# Blueberry_Pi.net
KiCad netlist of a schematic drawn in EAGLE
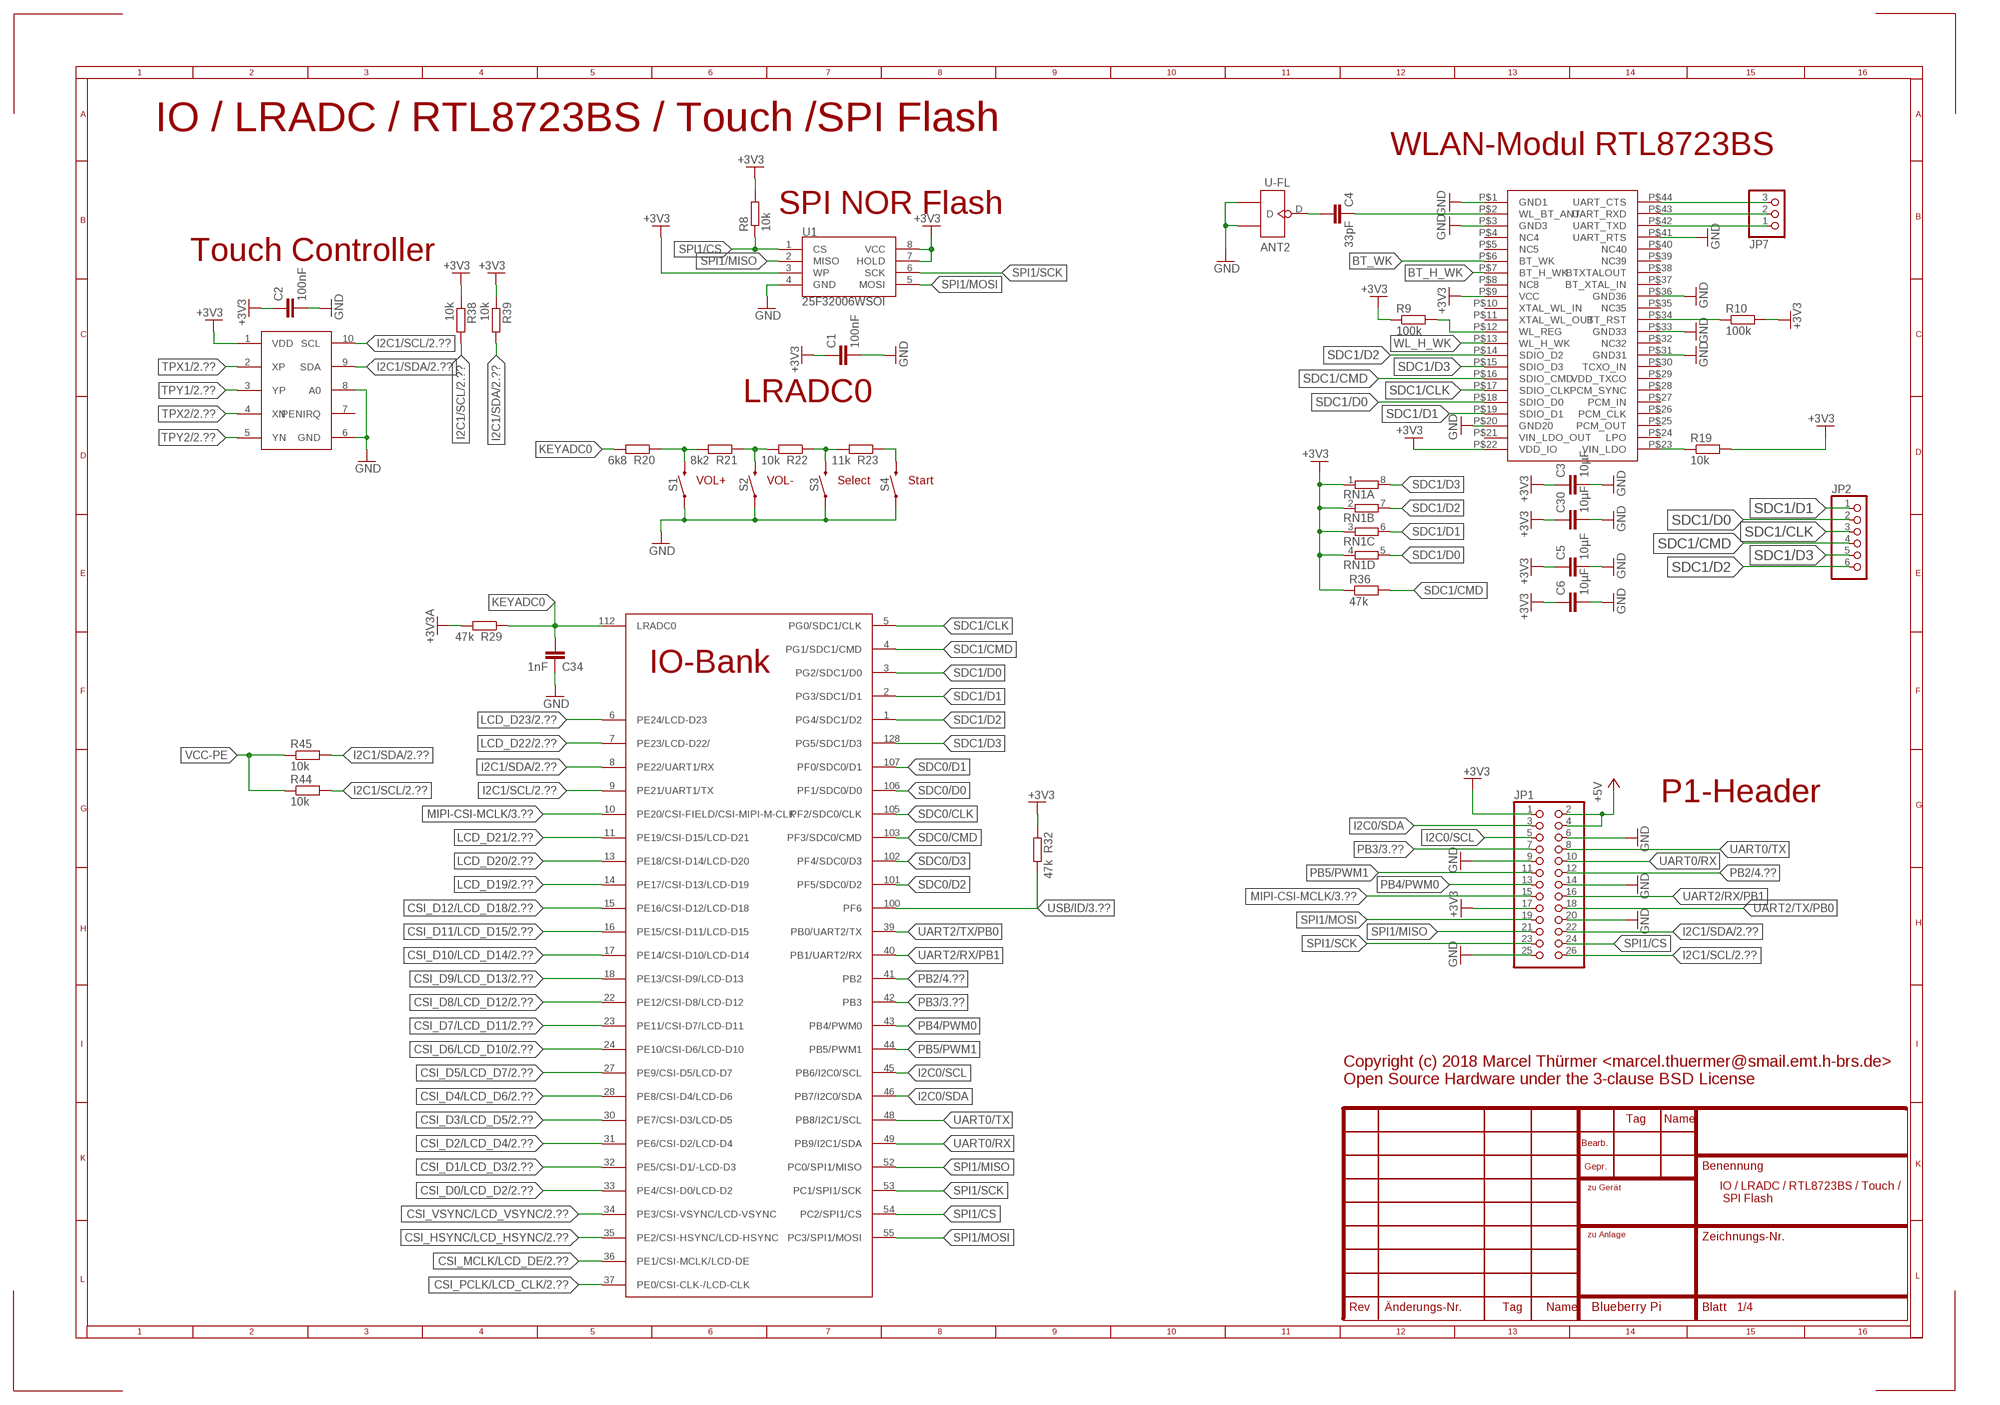
[diagram p0: schematic, sheet 1]
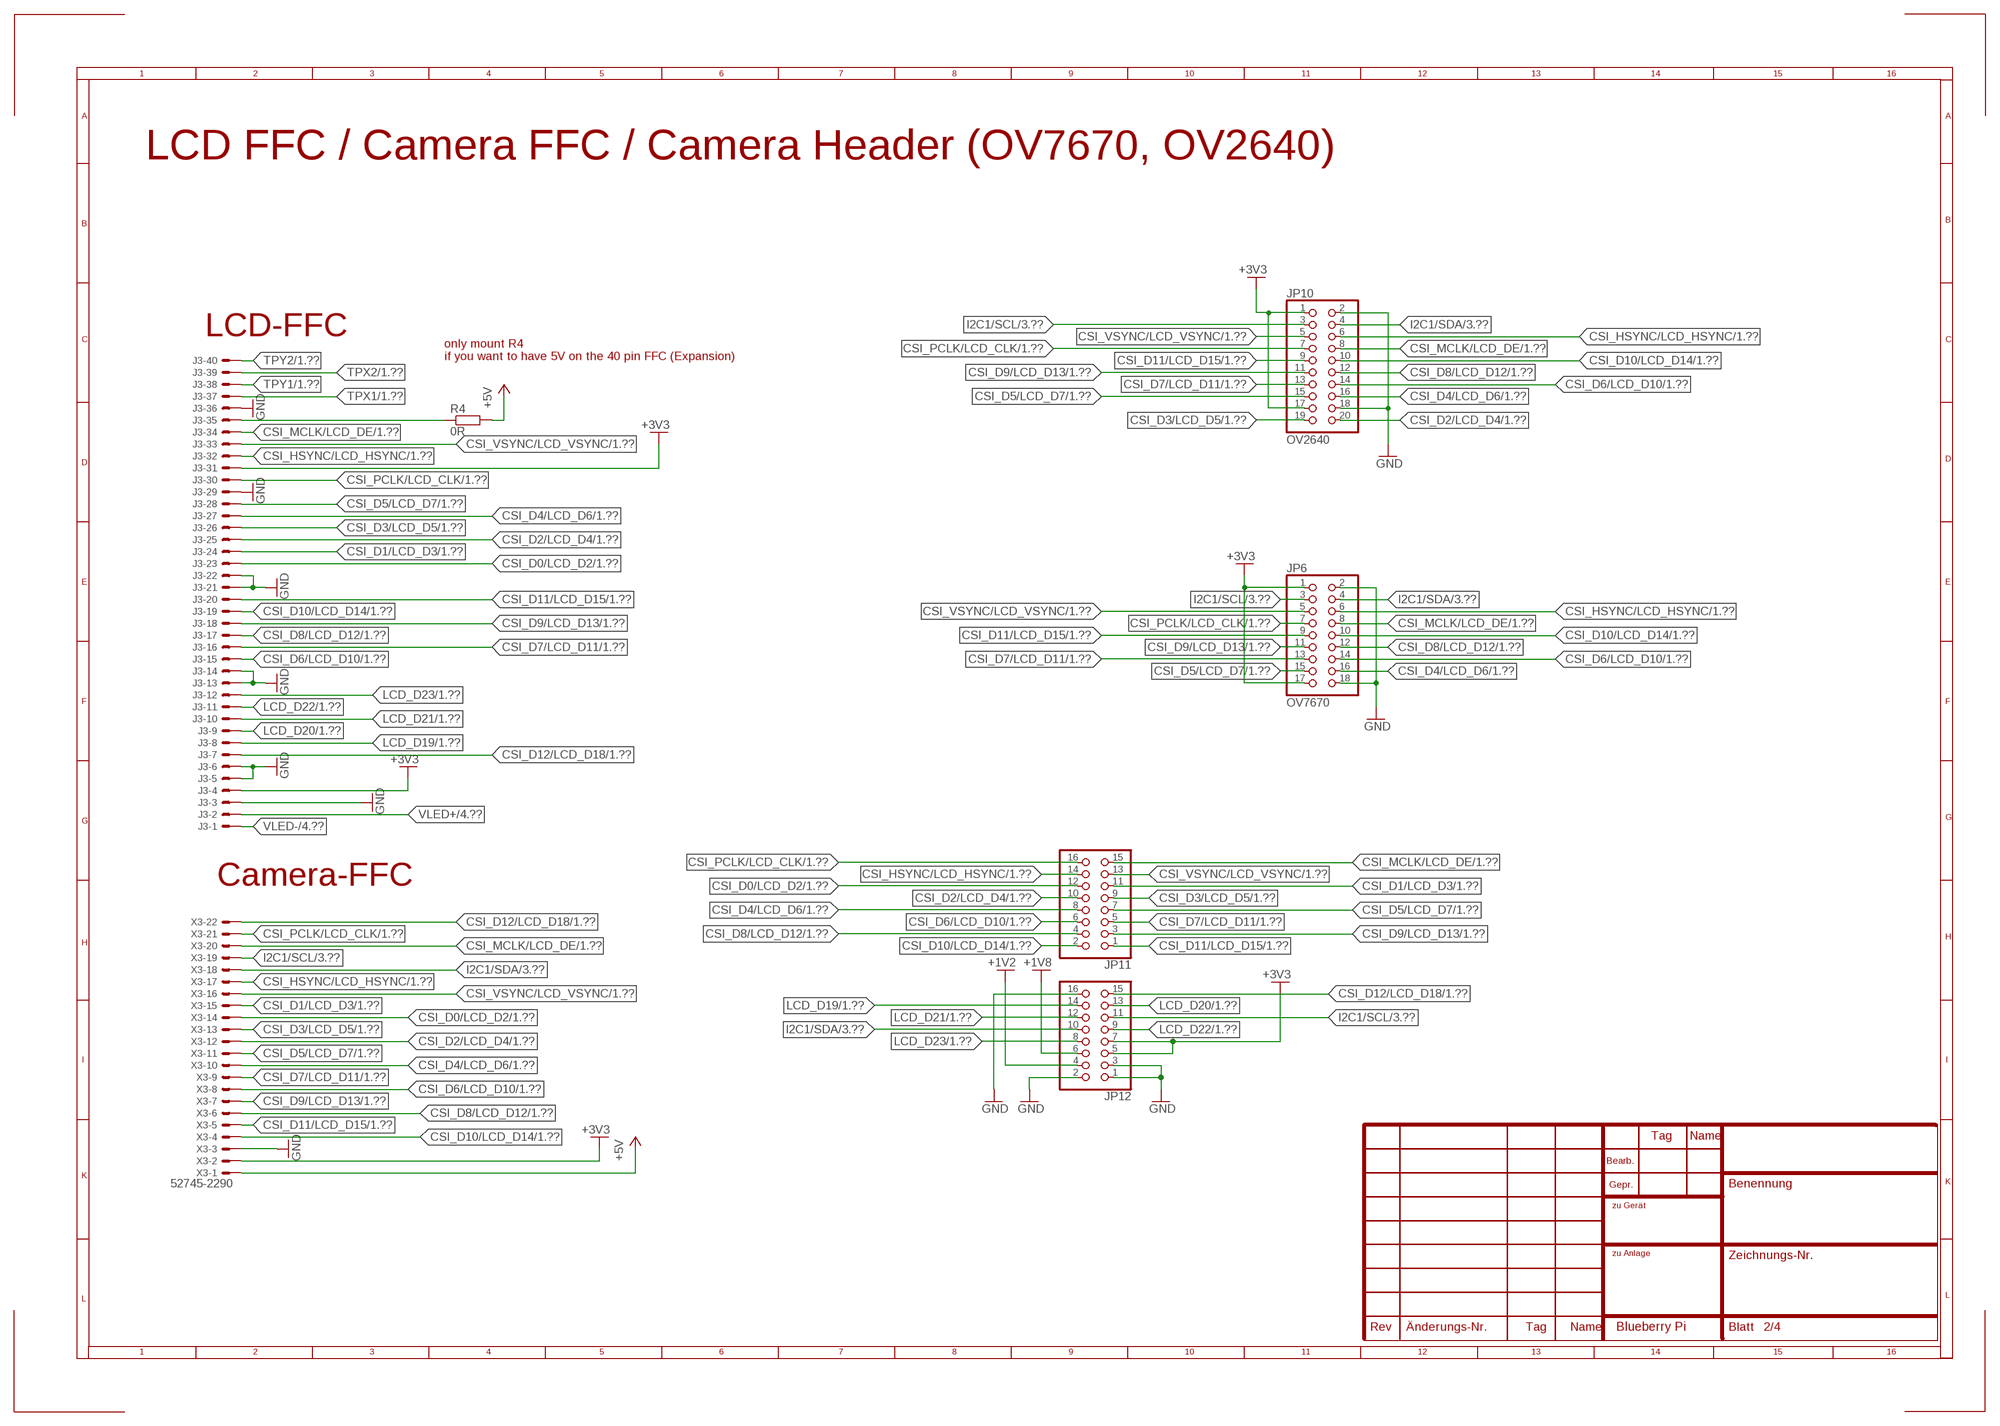
[diagram p1: schematic, sheet 2]
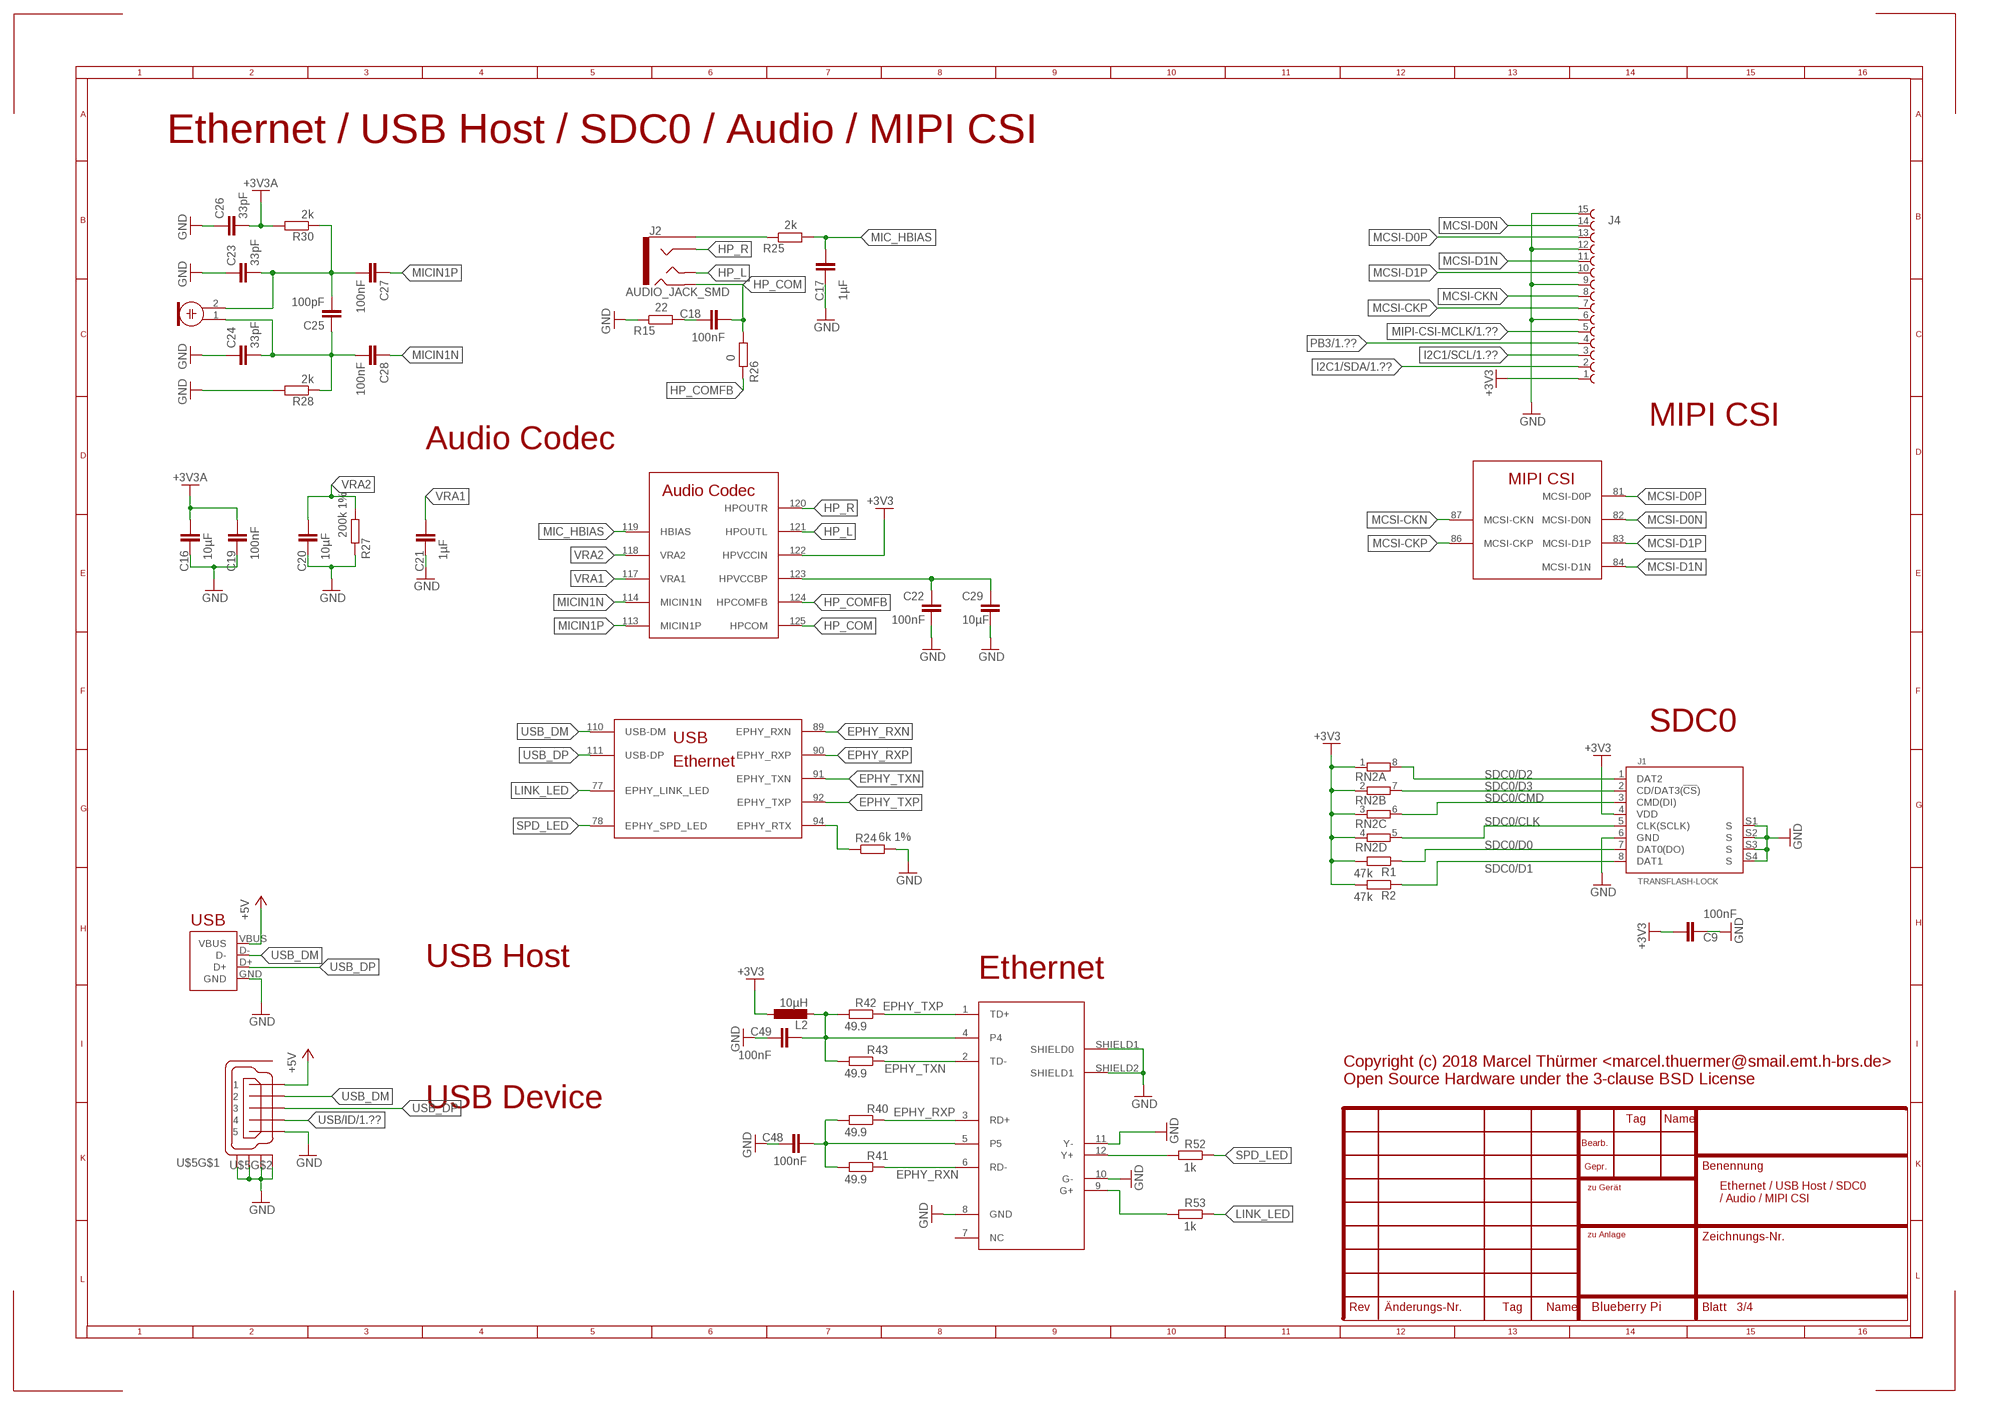
[diagram p2: schematic, sheet 3]
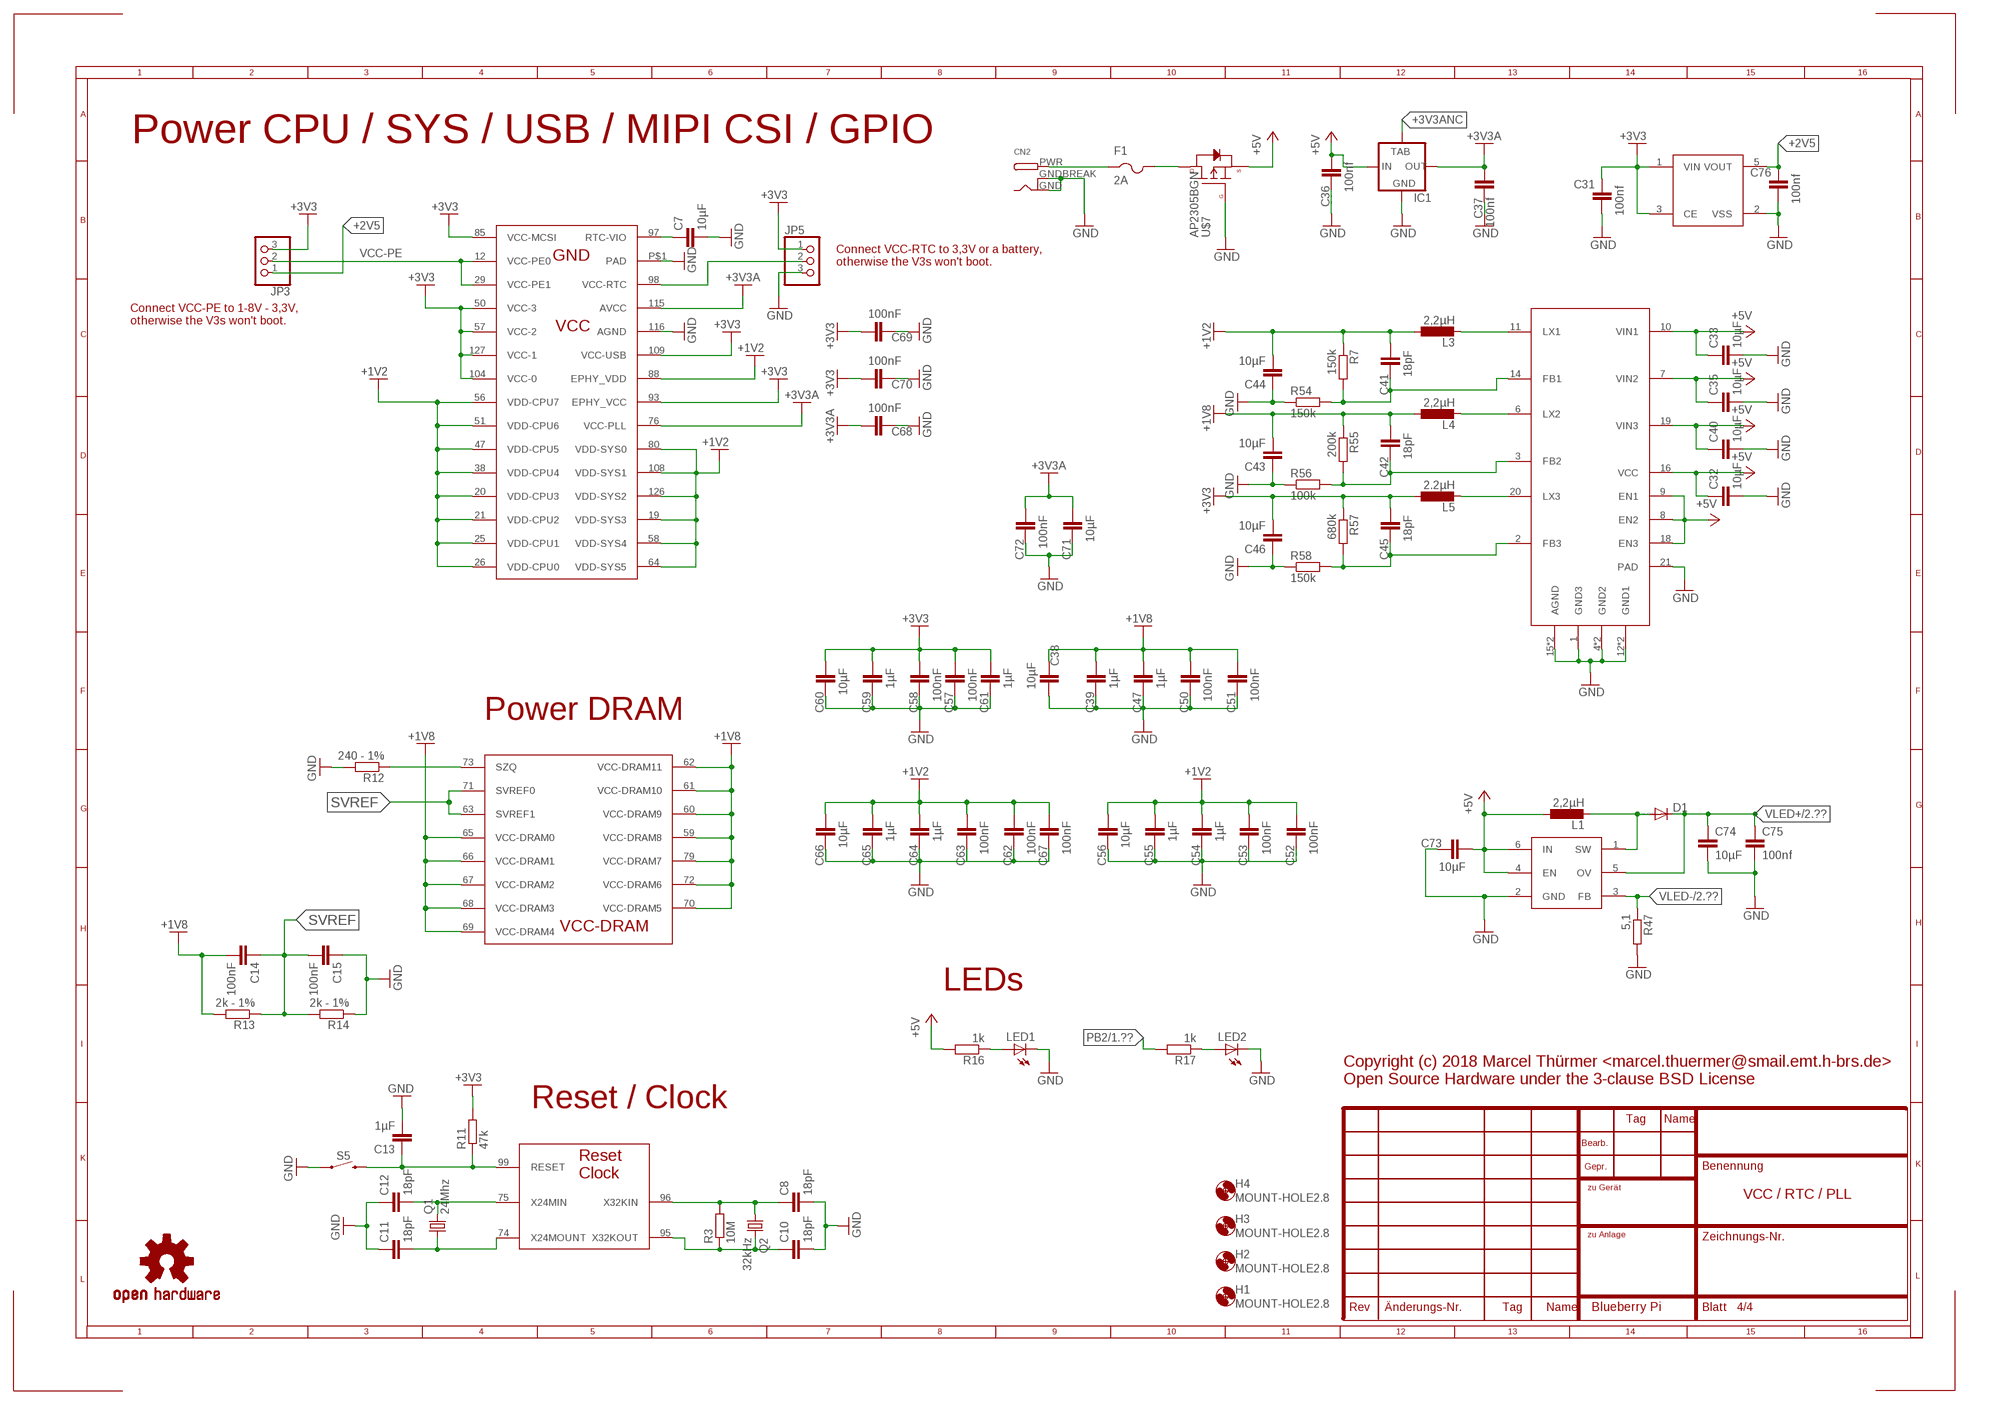
[diagram p3: schematic, sheet 4]

(export (version "E")
  (design (tool "Eeschema 10.0.6"))
  (components
    (comp (ref "C9")
      (value "100nF")
      (footprint "eagle-import:C0603")
      (libsource (lib "eagle-import") (part "C-EUC0603"))
    )
    (comp (ref "C16")
      (value "10µF")
      (footprint "eagle-import:C0805")
      (libsource (lib "eagle-import") (part "C-EUC0805"))
    )
    (comp (ref "C17")
      (value "1µF")
      (footprint "eagle-import:C0603")
      (libsource (lib "eagle-import") (part "C-EUC0603"))
    )
    (comp (ref "C18")
      (value "100nF")
      (footprint "eagle-import:C0603")
      (libsource (lib "eagle-import") (part "C-EUC0603"))
    )
    (comp (ref "C19")
      (value "100nF")
      (footprint "eagle-import:C0603")
      (libsource (lib "eagle-import") (part "C-EUC0603"))
    )
    (comp (ref "C20")
      (value "10µF")
      (footprint "eagle-import:C0805")
      (libsource (lib "eagle-import") (part "C-EUC0805"))
    )
    (comp (ref "C21")
      (value "1µF")
      (footprint "eagle-import:C0603")
      (libsource (lib "eagle-import") (part "C-EUC0603"))
    )
    (comp (ref "C22")
      (value "100nF")
      (footprint "eagle-import:C0603")
      (libsource (lib "eagle-import") (part "C-EUC0603"))
    )
    (comp (ref "C23")
      (value "33pF")
      (footprint "eagle-import:C0603")
      (libsource (lib "eagle-import") (part "C-EUC0603"))
    )
    (comp (ref "C24")
      (value "33pF")
      (footprint "eagle-import:C0603")
      (libsource (lib "eagle-import") (part "C-EUC0603"))
    )
    (comp (ref "C25")
      (value "100pF")
      (footprint "eagle-import:C0603")
      (libsource (lib "eagle-import") (part "C-EUC0603"))
    )
    (comp (ref "C26")
      (value "33pF")
      (footprint "eagle-import:C0603")
      (libsource (lib "eagle-import") (part "C-EUC0603"))
    )
    (comp (ref "C27")
      (value "100nF")
      (footprint "eagle-import:C0603")
      (libsource (lib "eagle-import") (part "C-EUC0603"))
    )
    (comp (ref "C28")
      (value "100nF")
      (footprint "eagle-import:C0603")
      (libsource (lib "eagle-import") (part "C-EUC0603"))
    )
    (comp (ref "C29")
      (value "10µF")
      (footprint "eagle-import:C0805")
      (libsource (lib "eagle-import") (part "C-EUC0805"))
    )
    (comp (ref "C48")
      (value "100nF")
      (footprint "eagle-import:C0603")
      (libsource (lib "eagle-import") (part "C-EUC0603"))
    )
    (comp (ref "C49")
      (value "100nF")
      (footprint "eagle-import:C0603")
      (libsource (lib "eagle-import") (part "C-EUC0603"))
    )
    (comp (ref "J1")
      (value "TRANSFLASH-LOCK")
      (footprint "eagle-import:TRANSFLASH-LOCK-SOCK")
      (libsource (lib "eagle-import") (part "TRANSFLASH-LOCK"))
    )
    (comp (ref "J2")
      (value "AUDIO_JACK_SMD")
      (footprint "eagle-import:AUDIO_JACK_3.5MM_TRRS_SMD_RA")
      (libsource (lib "eagle-import") (part "AUDIO_JACK_TRRSSMD_RA"))
    )
    (comp (ref "J4")
      (value "68611514122")
      (footprint "eagle-import:68611514122")
      (libsource (lib "eagle-import") (part "68611514122"))
    )
    (comp (ref "L2")
      (value "10µH")
      (footprint "eagle-import:L0805")
      (libsource (lib "eagle-import") (part "L-EUL0805"))
    )
    (comp (ref "MIC")
      (value "ELECTRET_MICROPHON-F6035AP")
      (footprint "eagle-import:F6035AP")
      (libsource (lib "eagle-import") (part "ELECTRET_MICROPHON-F6035AP"))
    )
    (comp (ref "R1")
      (value "47k")
      (footprint "eagle-import:R0603")
      (libsource (lib "eagle-import") (part "R-EU_R0603"))
    )
    (comp (ref "R2")
      (value "47k")
      (footprint "eagle-import:R0603")
      (libsource (lib "eagle-import") (part "R-EU_R0603"))
    )
    (comp (ref "R15")
      (value "22")
      (footprint "eagle-import:R0603")
      (libsource (lib "eagle-import") (part "R-EU_R0603"))
    )
    (comp (ref "R24")
      (value "6k 1%")
      (footprint "eagle-import:R0603")
      (libsource (lib "eagle-import") (part "R-EU_R0603"))
    )
    (comp (ref "R25")
      (value "2k")
      (footprint "eagle-import:R0603")
      (libsource (lib "eagle-import") (part "R-EU_R0603"))
    )
    (comp (ref "R26")
      (value "0")
      (footprint "eagle-import:R0603")
      (libsource (lib "eagle-import") (part "R-EU_R0603"))
    )
    (comp (ref "R27")
      (value "200k 1%")
      (footprint "eagle-import:R0603")
      (libsource (lib "eagle-import") (part "R-EU_R0603"))
    )
    (comp (ref "R28")
      (value "2k")
      (footprint "eagle-import:R0603")
      (libsource (lib "eagle-import") (part "R-EU_R0603"))
    )
    (comp (ref "R30")
      (value "2k")
      (footprint "eagle-import:R0603")
      (libsource (lib "eagle-import") (part "R-EU_R0603"))
    )
    (comp (ref "R40")
      (value "49.9")
      (footprint "eagle-import:R0603")
      (libsource (lib "eagle-import") (part "R-EU_R0603"))
    )
    (comp (ref "R41")
      (value "49.9")
      (footprint "eagle-import:R0603")
      (libsource (lib "eagle-import") (part "R-EU_R0603"))
    )
    (comp (ref "R42")
      (value "49.9")
      (footprint "eagle-import:R0603")
      (libsource (lib "eagle-import") (part "R-EU_R0603"))
    )
    (comp (ref "R43")
      (value "49.9")
      (footprint "eagle-import:R0603")
      (libsource (lib "eagle-import") (part "R-EU_R0603"))
    )
    (comp (ref "R52")
      (value "1k")
      (footprint "eagle-import:R0603")
      (libsource (lib "eagle-import") (part "R-EU_R0603"))
    )
    (comp (ref "R53")
      (value "1k")
      (footprint "eagle-import:R0603")
      (libsource (lib "eagle-import") (part "R-EU_R0603"))
    )
    (comp (ref "RN2")
      (value "4R-NEXB38V")
      (footprint "eagle-import:EXB38V")
      (libsource (lib "eagle-import") (part "4R-NEXB38V"))
    )
    (comp (ref "U$1")
      (value "V3S")
      (footprint "eagle-import:QFP-128")
      (libsource (lib "eagle-import") (part "V3S"))
    )
    (comp (ref "U$3")
      (value "HR911105A")
      (footprint "eagle-import:RJ45")
      (libsource (lib "eagle-import") (part "HR911105A"))
    )
    (comp (ref "U$5")
      (value "CON-HIROSE_MICRO-USB-SHIELD-ZX62R-B-5P")
      (footprint "eagle-import:CON-HIROSE_ZX62R-B-5P")
      (libsource (lib "eagle-import") (part "CON-HIROSE_MICRO-USB-SHIELD-ZX62R-B-5P"))
    )
    (comp (ref "X1")
      (value "USB-B-S")
      (footprint "eagle-import:USB-B-SMT")
      (libsource (lib "eagle-import") (part "USB-B-S"))
    )
    (comp (ref "C7")
      (value "10µF")
      (footprint "eagle-import:C0805")
      (libsource (lib "eagle-import") (part "C-EUC0805"))
    )
    (comp (ref "C8")
      (value "18pF")
      (footprint "eagle-import:C0603")
      (libsource (lib "eagle-import") (part "C-EUC0603"))
    )
    (comp (ref "C10")
      (value "18pF")
      (footprint "eagle-import:C0603")
      (libsource (lib "eagle-import") (part "C-EUC0603"))
    )
    (comp (ref "C11")
      (value "18pF")
      (footprint "eagle-import:C0603")
      (libsource (lib "eagle-import") (part "C-EUC0603"))
    )
    (comp (ref "C12")
      (value "18pF")
      (footprint "eagle-import:C0603")
      (libsource (lib "eagle-import") (part "C-EUC0603"))
    )
    (comp (ref "C13")
      (value "1µF")
      (footprint "eagle-import:C0603")
      (libsource (lib "eagle-import") (part "C-EUC0603"))
    )
    (comp (ref "C14")
      (value "100nF")
      (footprint "eagle-import:C0603")
      (libsource (lib "eagle-import") (part "C-EUC0603"))
    )
    (comp (ref "C15")
      (value "100nF")
      (footprint "eagle-import:C0603")
      (libsource (lib "eagle-import") (part "C-EUC0603"))
    )
    (comp (ref "C31")
      (value "100nf")
      (footprint "eagle-import:C0603")
      (libsource (lib "eagle-import") (part "C-EUC0603"))
    )
    (comp (ref "C32")
      (value "10µF")
      (footprint "eagle-import:C0805")
      (libsource (lib "eagle-import") (part "rcl_334_C-EUC0805"))
    )
    (comp (ref "C33")
      (value "10µF")
      (footprint "eagle-import:C0805")
      (libsource (lib "eagle-import") (part "rcl_334_C-EUC0805"))
    )
    (comp (ref "C35")
      (value "10µF")
      (footprint "eagle-import:C0805")
      (libsource (lib "eagle-import") (part "rcl_334_C-EUC0805"))
    )
    (comp (ref "C36")
      (value "100nf")
      (footprint "eagle-import:C0603")
      (libsource (lib "eagle-import") (part "C-EUC0603"))
    )
    (comp (ref "C37")
      (value "100nf")
      (footprint "eagle-import:C0603")
      (libsource (lib "eagle-import") (part "C-EUC0603"))
    )
    (comp (ref "C38")
      (value "10µF")
      (footprint "eagle-import:C0603")
      (libsource (lib "eagle-import") (part "C-EUC0603"))
    )
    (comp (ref "C39")
      (value "1µF")
      (footprint "eagle-import:C0603")
      (libsource (lib "eagle-import") (part "C-EUC0603"))
    )
    (comp (ref "C40")
      (value "10µF")
      (footprint "eagle-import:C0805")
      (libsource (lib "eagle-import") (part "rcl_334_C-EUC0805"))
    )
    (comp (ref "C41")
      (value "18pF")
      (footprint "eagle-import:C0603")
      (libsource (lib "eagle-import") (part "C-EUC0603"))
    )
    (comp (ref "C42")
      (value "18pF")
      (footprint "eagle-import:C0603")
      (libsource (lib "eagle-import") (part "C-EUC0603"))
    )
    (comp (ref "C43")
      (value "10µF")
      (footprint "eagle-import:C0805")
      (libsource (lib "eagle-import") (part "rcl_334_C-EUC0805"))
    )
    (comp (ref "C44")
      (value "10µF")
      (footprint "eagle-import:C0805")
      (libsource (lib "eagle-import") (part "rcl_334_C-EUC0805"))
    )
    (comp (ref "C45")
      (value "18pF")
      (footprint "eagle-import:C0603")
      (libsource (lib "eagle-import") (part "C-EUC0603"))
    )
    (comp (ref "C46")
      (value "10µF")
      (footprint "eagle-import:C0805")
      (libsource (lib "eagle-import") (part "rcl_334_C-EUC0805"))
    )
    (comp (ref "C47")
      (value "1µF")
      (footprint "eagle-import:C0603")
      (libsource (lib "eagle-import") (part "C-EUC0603"))
    )
    (comp (ref "C50")
      (value "100nF")
      (footprint "eagle-import:C0805")
      (libsource (lib "eagle-import") (part "C-EUC0805"))
    )
    (comp (ref "C51")
      (value "100nF")
      (footprint "eagle-import:C0603")
      (libsource (lib "eagle-import") (part "C-EUC0603"))
    )
    (comp (ref "C52")
      (value "100nF")
      (footprint "eagle-import:C0805")
      (libsource (lib "eagle-import") (part "C-EUC0805"))
    )
    (comp (ref "C53")
      (value "100nF")
      (footprint "eagle-import:C0603")
      (libsource (lib "eagle-import") (part "C-EUC0603"))
    )
    (comp (ref "C54")
      (value "1µF")
      (footprint "eagle-import:C0805")
      (libsource (lib "eagle-import") (part "C-EUC0805"))
    )
    (comp (ref "C55")
      (value "1µF")
      (footprint "eagle-import:C0603")
      (libsource (lib "eagle-import") (part "C-EUC0603"))
    )
    (comp (ref "C56")
      (value "10µF")
      (footprint "eagle-import:C0603")
      (libsource (lib "eagle-import") (part "C-EUC0603"))
    )
    (comp (ref "C57")
      (value "100nF")
      (footprint "eagle-import:C0603")
      (libsource (lib "eagle-import") (part "C-EUC0603"))
    )
    (comp (ref "C58")
      (value "100nF")
      (footprint "eagle-import:C0603")
      (libsource (lib "eagle-import") (part "C-EUC0603"))
    )
    (comp (ref "C59")
      (value "1µF")
      (footprint "eagle-import:C0805")
      (libsource (lib "eagle-import") (part "C-EUC0805"))
    )
    (comp (ref "C60")
      (value "10µF")
      (footprint "eagle-import:C0603")
      (libsource (lib "eagle-import") (part "C-EUC0603"))
    )
    (comp (ref "C61")
      (value "1µF")
      (footprint "eagle-import:C0805")
      (libsource (lib "eagle-import") (part "C-EUC0805"))
    )
    (comp (ref "C62")
      (value "100nF")
      (footprint "eagle-import:C0603")
      (libsource (lib "eagle-import") (part "C-EUC0603"))
    )
    (comp (ref "C63")
      (value "100nF")
      (footprint "eagle-import:C0805")
      (libsource (lib "eagle-import") (part "C-EUC0805"))
    )
    (comp (ref "C64")
      (value "1µF")
      (footprint "eagle-import:C0603")
      (libsource (lib "eagle-import") (part "C-EUC0603"))
    )
    (comp (ref "C65")
      (value "1µF")
      (footprint "eagle-import:C0603")
      (libsource (lib "eagle-import") (part "C-EUC0603"))
    )
    (comp (ref "C66")
      (value "10µF")
      (footprint "eagle-import:C0805")
      (libsource (lib "eagle-import") (part "C-EUC0805"))
    )
    (comp (ref "C67")
      (value "100nF")
      (footprint "eagle-import:C0603")
      (libsource (lib "eagle-import") (part "C-EUC0603"))
    )
    (comp (ref "C68")
      (value "100nF")
      (footprint "eagle-import:C0603")
      (libsource (lib "eagle-import") (part "C-EUC0603"))
    )
    (comp (ref "C69")
      (value "100nF")
      (footprint "eagle-import:C0805")
      (libsource (lib "eagle-import") (part "C-EUC0805"))
    )
    (comp (ref "C70")
      (value "100nF")
      (footprint "eagle-import:C0603")
      (libsource (lib "eagle-import") (part "C-EUC0603"))
    )
    (comp (ref "C71")
      (value "10µF")
      (footprint "eagle-import:C0603")
      (libsource (lib "eagle-import") (part "C-EUC0603"))
    )
    (comp (ref "C72")
      (value "100nF")
      (footprint "eagle-import:C0603")
      (libsource (lib "eagle-import") (part "C-EUC0603"))
    )
    (comp (ref "C73")
      (value "10µF")
      (footprint "eagle-import:C0805")
      (libsource (lib "eagle-import") (part "C-EUC0805"))
    )
    (comp (ref "C74")
      (value "10µF")
      (footprint "eagle-import:C0805")
      (libsource (lib "eagle-import") (part "C-EUC0805"))
    )
    (comp (ref "C75")
      (value "100nf")
      (footprint "eagle-import:C0603")
      (libsource (lib "eagle-import") (part "C-EUC0603"))
    )
    (comp (ref "C76")
      (value "100nf")
      (footprint "eagle-import:C0603")
      (libsource (lib "eagle-import") (part "C-EUC0603"))
    )
    (comp (ref "CN2")
      (value "DCBARRELPTH")
      (footprint "eagle-import:DCJACK_2MM_PTH")
      (libsource (lib "eagle-import") (part "DCBARRELPTH"))
    )
    (comp (ref "D1")
      (value "DIODE-SOD323-W")
      (footprint "eagle-import:SOD323-W")
      (libsource (lib "eagle-import") (part "DIODE-SOD323-W"))
    )
    (comp (ref "F1")
      (value "2A")
      (footprint "eagle-import:R1206")
      (libsource (lib "eagle-import") (part "PTCFUSE-1206"))
    )
    (comp (ref "H1")
      (value "MOUNT-HOLE2.8")
      (footprint "eagle-import:2,8")
      (libsource (lib "eagle-import") (part "MOUNT-HOLE2.8"))
    )
    (comp (ref "H2")
      (value "MOUNT-HOLE2.8")
      (footprint "eagle-import:2,8")
      (libsource (lib "eagle-import") (part "MOUNT-HOLE2.8"))
    )
    (comp (ref "H3")
      (value "MOUNT-HOLE2.8")
      (footprint "eagle-import:2,8")
      (libsource (lib "eagle-import") (part "holes_237_MOUNT-HOLE2.8"))
    )
    (comp (ref "H4")
      (value "MOUNT-HOLE2.8")
      (footprint "eagle-import:2,8")
      (libsource (lib "eagle-import") (part "MOUNT-HOLE2.8"))
    )
    (comp (ref "IC1")
      (value "LM1117")
      (footprint "eagle-import:SOT223")
      (libsource (lib "eagle-import") (part "LM1117"))
    )
    (comp (ref "JP3")
      (value "PINHD-1X3")
      (footprint "eagle-import:1X03")
      (libsource (lib "eagle-import") (part "PINHD-1X3"))
    )
    (comp (ref "JP5")
      (value "PINHD-1X3")
      (footprint "eagle-import:1X03")
      (libsource (lib "eagle-import") (part "PINHD-1X3"))
    )
    (comp (ref "L1")
      (value "2,2µH")
      (footprint "eagle-import:ODD-INDUCTOR")
      (libsource (lib "eagle-import") (part "L-EU"))
    )
    (comp (ref "L3")
      (value "2,2µH")
      (footprint "eagle-import:ODD-INDUCTOR")
      (libsource (lib "eagle-import") (part "L-EU"))
    )
    (comp (ref "L4")
      (value "2,2µH")
      (footprint "eagle-import:ODD-INDUCTOR")
      (libsource (lib "eagle-import") (part "L-EU"))
    )
    (comp (ref "L5")
      (value "2.2µH")
      (footprint "eagle-import:ODD-INDUCTOR")
      (libsource (lib "eagle-import") (part "L-EU"))
    )
    (comp (ref "LED1")
      (value "LEDCHIPLED_0805")
      (footprint "eagle-import:CHIPLED_0805")
      (libsource (lib "eagle-import") (part "LEDCHIPLED_0805"))
    )
    (comp (ref "LED2")
      (value "LEDCHIPLED_0805")
      (footprint "eagle-import:CHIPLED_0805")
      (libsource (lib "eagle-import") (part "LEDCHIPLED_0805"))
    )
    (comp (ref "LOGO2")
      (value "OSHW-LOGOL")
      (footprint "eagle-import:OSHW-LOGO-L")
      (libsource (lib "eagle-import") (part "OSHW-LOGOL"))
    )
    (comp (ref "Q1")
      (value "24Mhz")
      (footprint "eagle-import:HC49U-V")
      (libsource (lib "eagle-import") (part "CRYSTALHC49U-V"))
    )
    (comp (ref "Q2")
      (value "32kHz")
      (footprint "eagle-import:TC38H")
      (libsource (lib "eagle-import") (part "CRYSTALTC38H"))
    )
    (comp (ref "R3")
      (value "10M")
      (footprint "eagle-import:R0603")
      (libsource (lib "eagle-import") (part "R-EU_R0603"))
    )
    (comp (ref "R7")
      (value "150k")
      (footprint "eagle-import:R0603")
      (libsource (lib "eagle-import") (part "R-EU_R0603"))
    )
    (comp (ref "R11")
      (value "47k")
      (footprint "eagle-import:R0603")
      (libsource (lib "eagle-import") (part "R-EU_R0603"))
    )
    (comp (ref "R12")
      (value "240 - 1%")
      (footprint "eagle-import:R0603")
      (libsource (lib "eagle-import") (part "R-EU_R0603"))
    )
    (comp (ref "R13")
      (value "2k - 1%")
      (footprint "eagle-import:R0603")
      (libsource (lib "eagle-import") (part "R-EU_R0603"))
    )
    (comp (ref "R14")
      (value "2k - 1%")
      (footprint "eagle-import:R0603")
      (libsource (lib "eagle-import") (part "R-EU_R0603"))
    )
    (comp (ref "R16")
      (value "1k")
      (footprint "eagle-import:R0603")
      (libsource (lib "eagle-import") (part "R-EU_R0603"))
    )
    (comp (ref "R17")
      (value "1k")
      (footprint "eagle-import:R0603")
      (libsource (lib "eagle-import") (part "R-EU_R0603"))
    )
    (comp (ref "R47")
      (value "5,1")
      (footprint "eagle-import:R0603")
      (libsource (lib "eagle-import") (part "R-EU_R0603"))
    )
    (comp (ref "R54")
      (value "150k")
      (footprint "eagle-import:R0603")
      (libsource (lib "eagle-import") (part "R-EU_R0603"))
    )
    (comp (ref "R55")
      (value "200k")
      (footprint "eagle-import:R0603")
      (libsource (lib "eagle-import") (part "R-EU_R0603"))
    )
    (comp (ref "R56")
      (value "100k")
      (footprint "eagle-import:R0603")
      (libsource (lib "eagle-import") (part "R-EU_R0603"))
    )
    (comp (ref "R57")
      (value "680k")
      (footprint "eagle-import:R0603")
      (libsource (lib "eagle-import") (part "R-EU_R0603"))
    )
    (comp (ref "R58")
      (value "150k")
      (footprint "eagle-import:R0603")
      (libsource (lib "eagle-import") (part "R-EU_R0603"))
    )
    (comp (ref "S5")
      (value "MOMENTARY-SWITCH-SPST-SMD-6.0X3.5MM")
      (footprint "eagle-import:TACTILE_SWITCH_SMD_6.0X3.5MM")
      (libsource (lib "eagle-import") (part "MOMENTARY-SWITCH-SPST-SMD-6.0X3.5MM"))
    )
    (comp (ref "U$4")
      (value "EA3036")
      (footprint "eagle-import:QFN20")
      (libsource (lib "eagle-import") (part "EA3036"))
    )
    (comp (ref "U$6")
      (value "XC6204")
      (footprint "eagle-import:SOT25")
      (libsource (lib "eagle-import") (part "XC6204XC6204"))
    )
    (comp (ref "U$7")
      (value "AP2305BGN")
      (footprint "eagle-import:SOT23-3")
      (libsource (lib "eagle-import") (part "P-CHANNEL-MOSFET"))
    )
    (comp (ref "U$9")
      (value "PT4101")
      (footprint "eagle-import:SOT23-6")
      (libsource (lib "eagle-import") (part "PT4101"))
    )
    (comp (ref "ANT2")
      (value "U-FL")
      (footprint "eagle-import:U-FL3P-SMD-2.6X2.6X1.0MM")
      (libsource (lib "eagle-import") (part "ANTENNA-CONN-U-FL(3P)"))
    )
    (comp (ref "C1")
      (value "100nF")
      (footprint "eagle-import:C0603")
      (libsource (lib "eagle-import") (part "C-EUC0603"))
    )
    (comp (ref "C2")
      (value "100nF")
      (footprint "eagle-import:C0603")
      (libsource (lib "eagle-import") (part "C-EUC0603"))
    )
    (comp (ref "C3")
      (value "10µF")
      (footprint "eagle-import:C0805")
      (libsource (lib "eagle-import") (part "C-EUC0805"))
    )
    (comp (ref "C4")
      (value "33pF")
      (footprint "eagle-import:C0603")
      (libsource (lib "eagle-import") (part "C-EUC0603"))
    )
    (comp (ref "C5")
      (value "10µF")
      (footprint "eagle-import:C0805")
      (libsource (lib "eagle-import") (part "C-EUC0805"))
    )
    (comp (ref "C6")
      (value "10µF")
      (footprint "eagle-import:C0805")
      (libsource (lib "eagle-import") (part "C-EUC0805"))
    )
    (comp (ref "C30")
      (value "10µF")
      (footprint "eagle-import:C0805")
      (libsource (lib "eagle-import") (part "C-EUC0805"))
    )
    (comp (ref "C34")
      (value "1nF")
      (footprint "eagle-import:C0603")
      (libsource (lib "eagle-import") (part "C-EUC0603"))
    )
    (comp (ref "JP1")
      (value "PINHD-2X13")
      (footprint "eagle-import:2X13")
      (libsource (lib "eagle-import") (part "PINHD-2X13"))
    )
    (comp (ref "JP2")
      (value "PINHD-1X6_2.00")
      (footprint "eagle-import:1X06M")
      (libsource (lib "eagle-import") (part "PINHD-1X6_2.00"))
    )
    (comp (ref "JP7")
      (value "PINHD-1X3M")
      (footprint "eagle-import:1X03M")
      (libsource (lib "eagle-import") (part "PINHD-1X3M"))
    )
    (comp (ref "R8")
      (value "10k")
      (footprint "eagle-import:R0603")
      (libsource (lib "eagle-import") (part "R-EU_R0603"))
    )
    (comp (ref "R9")
      (value "100k")
      (footprint "eagle-import:R0603")
      (libsource (lib "eagle-import") (part "R-EU_R0603"))
    )
    (comp (ref "R10")
      (value "100k")
      (footprint "eagle-import:R0603")
      (libsource (lib "eagle-import") (part "R-EU_R0603"))
    )
    (comp (ref "R19")
      (value "10k")
      (footprint "eagle-import:R0603")
      (libsource (lib "eagle-import") (part "R-EU_R0603"))
    )
    (comp (ref "R20")
      (value "6k8")
      (footprint "eagle-import:R0603")
      (libsource (lib "eagle-import") (part "R-EU_R0603"))
    )
    (comp (ref "R21")
      (value "8k2")
      (footprint "eagle-import:R0603")
      (libsource (lib "eagle-import") (part "R-EU_R0603"))
    )
    (comp (ref "R22")
      (value "10k")
      (footprint "eagle-import:R0603")
      (libsource (lib "eagle-import") (part "R-EU_R0603"))
    )
    (comp (ref "R23")
      (value "11k")
      (footprint "eagle-import:R0603")
      (libsource (lib "eagle-import") (part "R-EU_R0603"))
    )
    (comp (ref "R29")
      (value "47k")
      (footprint "eagle-import:R0603")
      (libsource (lib "eagle-import") (part "R-EU_R0603"))
    )
    (comp (ref "R32")
      (value "47k")
      (footprint "eagle-import:R0603")
      (libsource (lib "eagle-import") (part "R-EU_R0603"))
    )
    (comp (ref "R36")
      (value "47k")
      (footprint "eagle-import:R0603")
      (libsource (lib "eagle-import") (part "R-EU_R0603"))
    )
    (comp (ref "R38")
      (value "10k")
      (footprint "eagle-import:R0603")
      (libsource (lib "eagle-import") (part "R-EU_R0603"))
    )
    (comp (ref "R39")
      (value "10k")
      (footprint "eagle-import:R0603")
      (libsource (lib "eagle-import") (part "R-EU_R0603"))
    )
    (comp (ref "R44")
      (value "10k")
      (footprint "eagle-import:R0603")
      (libsource (lib "eagle-import") (part "R-EU_R0603"))
    )
    (comp (ref "R45")
      (value "10k")
      (footprint "eagle-import:R0603")
      (libsource (lib "eagle-import") (part "R-EU_R0603"))
    )
    (comp (ref "RN1")
      (value "4R-NEXB38V")
      (footprint "eagle-import:EXB38V")
      (libsource (lib "eagle-import") (part "4R-NEXB38V"))
    )
    (comp (ref "S1")
      (value "MOMENTARY-SWITCH-SPST-SMD-6.0X3.5MM")
      (footprint "eagle-import:TACTILE_SWITCH_SMD_6.0X3.5MM")
      (libsource (lib "eagle-import") (part "MOMENTARY-SWITCH-SPST-SMD-6.0X3.5MM"))
    )
    (comp (ref "S2")
      (value "MOMENTARY-SWITCH-SPST-SMD-6.0X3.5MM")
      (footprint "eagle-import:TACTILE_SWITCH_SMD_6.0X3.5MM")
      (libsource (lib "eagle-import") (part "MOMENTARY-SWITCH-SPST-SMD-6.0X3.5MM"))
    )
    (comp (ref "S3")
      (value "MOMENTARY-SWITCH-SPST-SMD-6.0X3.5MM")
      (footprint "eagle-import:TACTILE_SWITCH_SMD_6.0X3.5MM")
      (libsource (lib "eagle-import") (part "MOMENTARY-SWITCH-SPST-SMD-6.0X3.5MM"))
    )
    (comp (ref "S4")
      (value "MOMENTARY-SWITCH-SPST-SMD-6.0X3.5MM")
      (footprint "eagle-import:TACTILE_SWITCH_SMD_6.0X3.5MM")
      (libsource (lib "eagle-import") (part "MOMENTARY-SWITCH-SPST-SMD-6.0X3.5MM"))
    )
    (comp (ref "U$2")
      (value "RTL8723BS")
      (footprint "eagle-import:LGA")
      (libsource (lib "eagle-import") (part "RTL8723BS"))
    )
    (comp (ref "U$8")
      (value "NS2009")
      (footprint "eagle-import:MSOP10")
      (libsource (lib "eagle-import") (part "NS2009"))
    )
    (comp (ref "U1")
      (value "25F32006WSOI")
      (footprint "eagle-import:SO08-EIAJ")
      (libsource (lib "eagle-import") (part "SPI_FLASH-X25XXSMD1"))
    )
    (comp (ref "J3")
      (value "40PINFPCH15-1LW")
      (footprint "eagle-import:XF2H-4015-1LW")
      (libsource (lib "eagle-import") (part "40PINFPC15-1LWH"))
    )
    (comp (ref "JP6")
      (value "OV7670")
      (footprint "eagle-import:2X09")
      (libsource (lib "eagle-import") (part "PINHD-2X9"))
    )
    (comp (ref "JP10")
      (value "OV2640")
      (footprint "eagle-import:2X10")
      (libsource (lib "eagle-import") (part "PINHD-2X10"))
    )
    (comp (ref "JP11")
      (value "PINHD-2X8M")
      (footprint "eagle-import:2X08M")
      (libsource (lib "eagle-import") (part "PINHD-2X8M"))
    )
    (comp (ref "JP12")
      (value "PINHD-2X8M")
      (footprint "eagle-import:2X08M")
      (libsource (lib "eagle-import") (part "PINHD-2X8M"))
    )
    (comp (ref "R4")
      (value "0R")
      (footprint "eagle-import:R0603")
      (libsource (lib "eagle-import") (part "R-EU_R0603"))
    )
    (comp (ref "X3")
      (value "52745-2290")
      (footprint "eagle-import:52745-2290")
      (libsource (lib "eagle-import") (part "52745-2290"))
    )
  )
  (nets
    (net (code "1") (name "+1V2") (class "Default")
      (node (ref "C41") (pin "1") (pinfunction "1_1") (pintype "passive"))
      (node (ref "C44") (pin "2") (pinfunction "2_2") (pintype "passive"))
      (node (ref "C52") (pin "1") (pinfunction "1_1") (pintype "passive"))
      (node (ref "C53") (pin "1") (pinfunction "1_1") (pintype "passive"))
      (node (ref "C54") (pin "1") (pinfunction "1_1") (pintype "passive"))
      (node (ref "C55") (pin "1") (pinfunction "1_1") (pintype "passive"))
      (node (ref "C56") (pin "1") (pinfunction "1_1") (pintype "passive"))
      (node (ref "C62") (pin "1") (pinfunction "1_1") (pintype "passive"))
      (node (ref "C63") (pin "1") (pinfunction "1_1") (pintype "passive"))
      (node (ref "C64") (pin "1") (pinfunction "1_1") (pintype "passive"))
      (node (ref "C65") (pin "1") (pinfunction "1_1") (pintype "passive"))
      (node (ref "C66") (pin "1") (pinfunction "1_1") (pintype "passive"))
      (node (ref "C67") (pin "1") (pinfunction "1_1") (pintype "passive"))
      (node (ref "JP12") (pin "4") (pinfunction "4_4") (pintype "passive"))
      (node (ref "L3") (pin "P$1") (pinfunction "1_P$1") (pintype "passive"))
      (node (ref "R7") (pin "1") (pinfunction "1_1") (pintype "passive"))
      (node (ref "U$1") (pin "108") (pinfunction "VDD-SYS1_108") (pintype "bidirectional"))
      (node (ref "U$1") (pin "126") (pinfunction "VDD-SYS2_126") (pintype "bidirectional"))
      (node (ref "U$1") (pin "19") (pinfunction "VDD-SYS3_19") (pintype "bidirectional"))
      (node (ref "U$1") (pin "20") (pinfunction "VDD-CPU3_20") (pintype "bidirectional"))
      (node (ref "U$1") (pin "21") (pinfunction "VDD-CPU2_21") (pintype "bidirectional"))
      (node (ref "U$1") (pin "25") (pinfunction "VDD-CPU1_25") (pintype "bidirectional"))
      (node (ref "U$1") (pin "26") (pinfunction "VDD-CPU0_26") (pintype "bidirectional"))
      (node (ref "U$1") (pin "38") (pinfunction "VDD-CPU4_38") (pintype "bidirectional"))
      (node (ref "U$1") (pin "47") (pinfunction "VDD-CPU5_47") (pintype "bidirectional"))
      (node (ref "U$1") (pin "51") (pinfunction "VDD-CPU6_51") (pintype "bidirectional"))
      (node (ref "U$1") (pin "56") (pinfunction "VDD-CPU7_56") (pintype "bidirectional"))
      (node (ref "U$1") (pin "58") (pinfunction "VDD-SYS4_58") (pintype "bidirectional"))
      (node (ref "U$1") (pin "64") (pinfunction "VDD-SYS5_64") (pintype "bidirectional"))
      (node (ref "U$1") (pin "80") (pinfunction "VDD-SYS0_80") (pintype "bidirectional"))
      (node (ref "U$1") (pin "88") (pinfunction "EPHY_VDD_88") (pintype "bidirectional"))
    )
    (net (code "2") (name "+1V8") (class "Default")
      (node (ref "C14") (pin "2") (pinfunction "2_2") (pintype "passive"))
      (node (ref "C38") (pin "2") (pinfunction "2_2") (pintype "passive"))
      (node (ref "C39") (pin "1") (pinfunction "1_1") (pintype "passive"))
      (node (ref "C42") (pin "1") (pinfunction "1_1") (pintype "passive"))
      (node (ref "C43") (pin "2") (pinfunction "2_2") (pintype "passive"))
      (node (ref "C47") (pin "1") (pinfunction "1_1") (pintype "passive"))
      (node (ref "C50") (pin "1") (pinfunction "1_1") (pintype "passive"))
      (node (ref "C51") (pin "1") (pinfunction "1_1") (pintype "passive"))
      (node (ref "JP12") (pin "6") (pinfunction "6_6") (pintype "passive"))
      (node (ref "L4") (pin "P$1") (pinfunction "1_P$1") (pintype "passive"))
      (node (ref "R13") (pin "2") (pinfunction "2_2") (pintype "passive"))
      (node (ref "R55") (pin "1") (pinfunction "1_1") (pintype "passive"))
      (node (ref "U$1") (pin "59") (pinfunction "VCC-DRAM8_59") (pintype "bidirectional"))
      (node (ref "U$1") (pin "60") (pinfunction "VCC-DRAM9_60") (pintype "bidirectional"))
      (node (ref "U$1") (pin "61") (pinfunction "VCC-DRAM10_61") (pintype "bidirectional"))
      (node (ref "U$1") (pin "62") (pinfunction "VCC-DRAM11_62") (pintype "bidirectional"))
      (node (ref "U$1") (pin "65") (pinfunction "VCC-DRAM0_65") (pintype "bidirectional"))
      (node (ref "U$1") (pin "66") (pinfunction "VCC-DRAM1_66") (pintype "bidirectional"))
      (node (ref "U$1") (pin "67") (pinfunction "VCC-DRAM2_67") (pintype "bidirectional"))
      (node (ref "U$1") (pin "68") (pinfunction "VCC-DRAM3_68") (pintype "bidirectional"))
      (node (ref "U$1") (pin "69") (pinfunction "VCC-DRAM4_69") (pintype "bidirectional"))
      (node (ref "U$1") (pin "70") (pinfunction "VCC-DRAM5_70") (pintype "bidirectional"))
      (node (ref "U$1") (pin "72") (pinfunction "VCC-DRAM6_72") (pintype "bidirectional"))
      (node (ref "U$1") (pin "79") (pinfunction "VCC-DRAM7_79") (pintype "bidirectional"))
    )
    (net (code "3") (name "+2V5") (class "Default")
      (node (ref "C76") (pin "1") (pinfunction "1_1") (pintype "passive"))
      (node (ref "JP3") (pin "1") (pinfunction "1_1") (pintype "passive"))
      (node (ref "U$6") (pin "5") (pinfunction "VOUT_5") (pintype "bidirectional"))
    )
    (net (code "4") (name "+3V3") (class "Default")
      (node (ref "C1") (pin "1") (pinfunction "1_1") (pintype "passive"))
      (node (ref "C2") (pin "1") (pinfunction "1_1") (pintype "passive"))
      (node (ref "C3") (pin "1") (pinfunction "1_1") (pintype "passive"))
      (node (ref "C30") (pin "1") (pinfunction "1_1") (pintype "passive"))
      (node (ref "C31") (pin "1") (pinfunction "1_1") (pintype "passive"))
      (node (ref "C45") (pin "1") (pinfunction "1_1") (pintype "passive"))
      (node (ref "C46") (pin "2") (pinfunction "2_2") (pintype "passive"))
      (node (ref "C5") (pin "1") (pinfunction "1_1") (pintype "passive"))
      (node (ref "C57") (pin "1") (pinfunction "1_1") (pintype "passive"))
      (node (ref "C58") (pin "1") (pinfunction "1_1") (pintype "passive"))
      (node (ref "C59") (pin "1") (pinfunction "1_1") (pintype "passive"))
      (node (ref "C6") (pin "1") (pinfunction "1_1") (pintype "passive"))
      (node (ref "C60") (pin "1") (pinfunction "1_1") (pintype "passive"))
      (node (ref "C61") (pin "1") (pinfunction "1_1") (pintype "passive"))
      (node (ref "C69") (pin "1") (pinfunction "1_1") (pintype "passive"))
      (node (ref "C70") (pin "1") (pinfunction "1_1") (pintype "passive"))
      (node (ref "C9") (pin "1") (pinfunction "1_1") (pintype "passive"))
      (node (ref "J1") (pin "4") (pinfunction "VDD_4") (pintype "power_in"))
      (node (ref "J3") (pin "31") (pinfunction "MS_31") (pintype "passive"))
      (node (ref "J3") (pin "4") (pinfunction "MS_4") (pintype "passive"))
      (node (ref "J4") (pin "1") (pinfunction "15_1") (pintype "passive"))
      (node (ref "JP1") (pin "1") (pinfunction "1_1") (pintype "passive"))
      (node (ref "JP1") (pin "17") (pinfunction "17_17") (pintype "passive"))
      (node (ref "JP10") (pin "1") (pinfunction "1_1") (pintype "passive"))
      (node (ref "JP10") (pin "17") (pinfunction "17_17") (pintype "passive"))
      (node (ref "JP12") (pin "5") (pinfunction "5_5") (pintype "passive"))
      (node (ref "JP12") (pin "7") (pinfunction "7_7") (pintype "passive"))
      (node (ref "JP3") (pin "3") (pinfunction "3_3") (pintype "passive"))
      (node (ref "JP5") (pin "1") (pinfunction "1_1") (pintype "passive"))
      (node (ref "JP6") (pin "1") (pinfunction "1_1") (pintype "passive"))
      (node (ref "JP6") (pin "17") (pinfunction "17_17") (pintype "passive"))
      (node (ref "L2") (pin "1") (pinfunction "1_1") (pintype "passive"))
      (node (ref "L5") (pin "P$1") (pinfunction "1_P$1") (pintype "passive"))
      (node (ref "R1") (pin "2") (pinfunction "2_2") (pintype "passive"))
      (node (ref "R10") (pin "2") (pinfunction "2_2") (pintype "passive"))
      (node (ref "R11") (pin "2") (pinfunction "2_2") (pintype "passive"))
      (node (ref "R19") (pin "2") (pinfunction "2_2") (pintype "passive"))
      (node (ref "R2") (pin "2") (pinfunction "2_2") (pintype "passive"))
      (node (ref "R32") (pin "1") (pinfunction "1_1") (pintype "passive"))
      (node (ref "R36") (pin "1") (pinfunction "1_1") (pintype "passive"))
      (node (ref "R38") (pin "1") (pinfunction "1_1") (pintype "passive"))
      (node (ref "R39") (pin "1") (pinfunction "1_1") (pintype "passive"))
      (node (ref "R57") (pin "1") (pinfunction "1_1") (pintype "passive"))
      (node (ref "R8") (pin "2") (pinfunction "2_2") (pintype "passive"))
      (node (ref "R9") (pin "1") (pinfunction "1_1") (pintype "passive"))
      (node (ref "RN1") (pin "1") (pinfunction "1_1") (pintype "passive"))
      (node (ref "RN1") (pin "2") (pinfunction "1_2") (pintype "passive"))
      (node (ref "RN1") (pin "3") (pinfunction "1_3") (pintype "passive"))
      (node (ref "RN1") (pin "4") (pinfunction "1_4") (pintype "passive"))
      (node (ref "RN2") (pin "1") (pinfunction "1_1") (pintype "passive"))
      (node (ref "RN2") (pin "2") (pinfunction "1_2") (pintype "passive"))
      (node (ref "RN2") (pin "3") (pinfunction "1_3") (pintype "passive"))
      (node (ref "RN2") (pin "4") (pinfunction "1_4") (pintype "passive"))
      (node (ref "U$1") (pin "104") (pinfunction "VCC-0_104") (pintype "bidirectional"))
      (node (ref "U$1") (pin "109") (pinfunction "VCC-USB_109") (pintype "bidirectional"))
      (node (ref "U$1") (pin "122") (pinfunction "HPVCCIN_122") (pintype "bidirectional"))
      (node (ref "U$1") (pin "127") (pinfunction "VCC-1_127") (pintype "bidirectional"))
      (node (ref "U$1") (pin "50") (pinfunction "VCC-3_50") (pintype "bidirectional"))
      (node (ref "U$1") (pin "57") (pinfunction "VCC-2_57") (pintype "bidirectional"))
      (node (ref "U$1") (pin "85") (pinfunction "VCC-MCSI_85") (pintype "bidirectional"))
      (node (ref "U$1") (pin "93") (pinfunction "EPHY_VCC_93") (pintype "bidirectional"))
      (node (ref "U$2") (pin "P$22") (pinfunction "VDD_IO_P$22") (pintype "bidirectional"))
      (node (ref "U$2") (pin "P$9") (pinfunction "VCC_P$9") (pintype "bidirectional"))
      (node (ref "U$6") (pin "1") (pinfunction "VIN_1") (pintype "bidirectional"))
      (node (ref "U$6") (pin "3") (pinfunction "CE_3") (pintype "bidirectional"))
      (node (ref "U$8") (pin "1") (pinfunction "VDD_1") (pintype "bidirectional"))
      (node (ref "U1") (pin "3") (pinfunction "WP_3") (pintype "bidirectional"))
      (node (ref "U1") (pin "7") (pinfunction "HOLD_7") (pintype "bidirectional"))
      (node (ref "U1") (pin "8") (pinfunction "VCC_8") (pintype "power_in"))
      (node (ref "X3") (pin "2") (pinfunction "S_2") (pintype "passive"))
    )
    (net (code "5") (name "+3V3A") (class "Default")
      (node (ref "C16") (pin "2") (pinfunction "2_2") (pintype "passive"))
      (node (ref "C19") (pin "2") (pinfunction "2_2") (pintype "passive"))
      (node (ref "C26") (pin "2") (pinfunction "2_2") (pintype "passive"))
      (node (ref "C37") (pin "1") (pinfunction "1_1") (pintype "passive"))
      (node (ref "C68") (pin "1") (pinfunction "1_1") (pintype "passive"))
      (node (ref "C71") (pin "1") (pinfunction "1_1") (pintype "passive"))
      (node (ref "C72") (pin "1") (pinfunction "1_1") (pintype "passive"))
      (node (ref "IC1") (pin "2") (pinfunction "OUT_2") (pintype "passive"))
      (node (ref "R29") (pin "2") (pinfunction "2_2") (pintype "passive"))
      (node (ref "R30") (pin "2") (pinfunction "2_2") (pintype "passive"))
      (node (ref "U$1") (pin "115") (pinfunction "AVCC_115") (pintype "bidirectional"))
      (node (ref "U$1") (pin "76") (pinfunction "VCC-PLL_76") (pintype "bidirectional"))
    )
    (net (code "6") (name "+3V3ANC") (class "Default")
      (node (ref "IC1") (pin "4") (pinfunction "IN1_4") (pintype "input"))
    )
    (net (code "7") (name "+5V") (class "Default")
      (node (ref "C32") (pin "1") (pinfunction "1_1") (pintype "passive"))
      (node (ref "C33") (pin "1") (pinfunction "1_1") (pintype "passive"))
      (node (ref "C35") (pin "1") (pinfunction "1_1") (pintype "passive"))
      (node (ref "C36") (pin "1") (pinfunction "1_1") (pintype "passive"))
      (node (ref "C40") (pin "1") (pinfunction "1_1") (pintype "passive"))
      (node (ref "C73") (pin "1") (pinfunction "1_1") (pintype "passive"))
      (node (ref "IC1") (pin "3") (pinfunction "IN_3") (pintype "input"))
      (node (ref "JP1") (pin "2") (pinfunction "2_2") (pintype "passive"))
      (node (ref "JP1") (pin "4") (pinfunction "4_4") (pintype "passive"))
      (node (ref "L1") (pin "P$1") (pinfunction "1_P$1") (pintype "passive"))
      (node (ref "R16") (pin "2") (pinfunction "2_2") (pintype "passive"))
      (node (ref "R4") (pin "2") (pinfunction "2_2") (pintype "passive"))
      (node (ref "U$4") (pin "10") (pinfunction "VIN1_10") (pintype "bidirectional"))
      (node (ref "U$4") (pin "16") (pinfunction "VCC_16") (pintype "bidirectional"))
      (node (ref "U$4") (pin "18") (pinfunction "EN3_18") (pintype "bidirectional"))
      (node (ref "U$4") (pin "19") (pinfunction "VIN3_19") (pintype "bidirectional"))
      (node (ref "U$4") (pin "7") (pinfunction "VIN2_7") (pintype "bidirectional"))
      (node (ref "U$4") (pin "8") (pinfunction "EN2_8") (pintype "bidirectional"))
      (node (ref "U$4") (pin "9") (pinfunction "EN1_9") (pintype "bidirectional"))
      (node (ref "U$5") (pin "1") (pinfunction "1_1") (pintype "input"))
      (node (ref "U$7") (pin "2") (pinfunction "S_2") (pintype "passive"))
      (node (ref "U$9") (pin "4") (pinfunction "EN_4") (pintype "bidirectional"))
      (node (ref "U$9") (pin "6") (pinfunction "IN_6") (pintype "bidirectional"))
      (node (ref "X1") (pin "VBUS") (pinfunction "VBUS_VBUS") (pintype "power_in"))
      (node (ref "X3") (pin "1") (pinfunction "S_1") (pintype "passive"))
    )
    (net (code "8") (name "BT_H_WK") (class "Default")
      (node (ref "U$2") (pin "P$7") (pinfunction "BT_H_WK_P$7") (pintype "bidirectional"))
    )
    (net (code "9") (name "BT_WK") (class "Default")
      (node (ref "U$2") (pin "P$6") (pinfunction "BT_WK_P$6") (pintype "bidirectional"))
    )
    (net (code "10") (name "CSI_D0{slash}LCD_D2") (class "Default")
      (node (ref "J3") (pin "23") (pinfunction "MS_23") (pintype "passive"))
      (node (ref "JP11") (pin "12") (pinfunction "12_12") (pintype "passive"))
      (node (ref "U$1") (pin "33") (pinfunction "PE4/CSI-D0/LCD-D2_33") (pintype "bidirectional"))
      (node (ref "X3") (pin "14") (pinfunction "S_14") (pintype "passive"))
    )
    (net (code "11") (name "CSI_D1{slash}LCD_D3") (class "Default")
      (node (ref "J3") (pin "24") (pinfunction "MS_24") (pintype "passive"))
      (node (ref "JP11") (pin "11") (pinfunction "11_11") (pintype "passive"))
      (node (ref "U$1") (pin "32") (pinfunction "PE5/CSI-D1/-LCD-D3_32") (pintype "bidirectional"))
      (node (ref "X3") (pin "15") (pinfunction "S_15") (pintype "passive"))
    )
    (net (code "12") (name "CSI_D2{slash}LCD_D4") (class "Default")
      (node (ref "J3") (pin "25") (pinfunction "MS_25") (pintype "passive"))
      (node (ref "JP10") (pin "20") (pinfunction "20_20") (pintype "passive"))
      (node (ref "JP11") (pin "10") (pinfunction "10_10") (pintype "passive"))
      (node (ref "U$1") (pin "31") (pinfunction "PE6/CSI-D2/LCD-D4_31") (pintype "bidirectional"))
      (node (ref "X3") (pin "12") (pinfunction "S_12") (pintype "passive"))
    )
    (net (code "13") (name "CSI_D3{slash}LCD_D5") (class "Default")
      (node (ref "J3") (pin "26") (pinfunction "MS_26") (pintype "passive"))
      (node (ref "JP10") (pin "19") (pinfunction "19_19") (pintype "passive"))
      (node (ref "JP11") (pin "9") (pinfunction "9_9") (pintype "passive"))
      (node (ref "U$1") (pin "30") (pinfunction "PE7/CSI-D3/LCD-D5_30") (pintype "bidirectional"))
      (node (ref "X3") (pin "13") (pinfunction "S_13") (pintype "passive"))
    )
    (net (code "14") (name "CSI_D4{slash}LCD_D6") (class "Default")
      (node (ref "J3") (pin "27") (pinfunction "MS_27") (pintype "passive"))
      (node (ref "JP10") (pin "16") (pinfunction "16_16") (pintype "passive"))
      (node (ref "JP11") (pin "8") (pinfunction "8_8") (pintype "passive"))
      (node (ref "JP6") (pin "16") (pinfunction "16_16") (pintype "passive"))
      (node (ref "U$1") (pin "28") (pinfunction "PE8/CSI-D4/LCD-D6_28") (pintype "bidirectional"))
      (node (ref "X3") (pin "10") (pinfunction "S_10") (pintype "passive"))
    )
    (net (code "15") (name "CSI_D5{slash}LCD_D7") (class "Default")
      (node (ref "J3") (pin "28") (pinfunction "MS_28") (pintype "passive"))
      (node (ref "JP10") (pin "15") (pinfunction "15_15") (pintype "passive"))
      (node (ref "JP11") (pin "7") (pinfunction "7_7") (pintype "passive"))
      (node (ref "JP6") (pin "15") (pinfunction "15_15") (pintype "passive"))
      (node (ref "U$1") (pin "27") (pinfunction "PE9/CSI-D5/LCD-D7_27") (pintype "bidirectional"))
      (node (ref "X3") (pin "11") (pinfunction "S_11") (pintype "passive"))
    )
    (net (code "16") (name "CSI_D6{slash}LCD_D10") (class "Default")
      (node (ref "J3") (pin "15") (pinfunction "MS_15") (pintype "passive"))
      (node (ref "JP10") (pin "14") (pinfunction "14_14") (pintype "passive"))
      (node (ref "JP11") (pin "6") (pinfunction "6_6") (pintype "passive"))
      (node (ref "JP6") (pin "14") (pinfunction "14_14") (pintype "passive"))
      (node (ref "U$1") (pin "24") (pinfunction "PE10/CSI-D6/LCD-D10_24") (pintype "bidirectional"))
      (node (ref "X3") (pin "8") (pinfunction "S_8") (pintype "passive"))
    )
    (net (code "17") (name "CSI_D7{slash}LCD_D11") (class "Default")
      (node (ref "J3") (pin "16") (pinfunction "MS_16") (pintype "passive"))
      (node (ref "JP10") (pin "13") (pinfunction "13_13") (pintype "passive"))
      (node (ref "JP11") (pin "5") (pinfunction "5_5") (pintype "passive"))
      (node (ref "JP6") (pin "13") (pinfunction "13_13") (pintype "passive"))
      (node (ref "U$1") (pin "23") (pinfunction "PE11/CSI-D7/LCD-D11_23") (pintype "bidirectional"))
      (node (ref "X3") (pin "9") (pinfunction "S_9") (pintype "passive"))
    )
    (net (code "18") (name "CSI_D8{slash}LCD_D12") (class "Default")
      (node (ref "J3") (pin "17") (pinfunction "MS_17") (pintype "passive"))
      (node (ref "JP10") (pin "12") (pinfunction "12_12") (pintype "passive"))
      (node (ref "JP11") (pin "4") (pinfunction "4_4") (pintype "passive"))
      (node (ref "JP6") (pin "12") (pinfunction "12_12") (pintype "passive"))
      (node (ref "U$1") (pin "22") (pinfunction "PE12/CSI-D8/LCD-D12_22") (pintype "bidirectional"))
      (node (ref "X3") (pin "6") (pinfunction "S_6") (pintype "passive"))
    )
    (net (code "19") (name "CSI_D9{slash}LCD_D13") (class "Default")
      (node (ref "J3") (pin "18") (pinfunction "MS_18") (pintype "passive"))
      (node (ref "JP10") (pin "11") (pinfunction "11_11") (pintype "passive"))
      (node (ref "JP11") (pin "3") (pinfunction "3_3") (pintype "passive"))
      (node (ref "JP6") (pin "11") (pinfunction "11_11") (pintype "passive"))
      (node (ref "U$1") (pin "18") (pinfunction "PE13/CSI-D9/LCD-D13_18") (pintype "bidirectional"))
      (node (ref "X3") (pin "7") (pinfunction "S_7") (pintype "passive"))
    )
    (net (code "20") (name "CSI_D10{slash}LCD_D14") (class "Default")
      (node (ref "J3") (pin "19") (pinfunction "MS_19") (pintype "passive"))
      (node (ref "JP10") (pin "10") (pinfunction "10_10") (pintype "passive"))
      (node (ref "JP11") (pin "2") (pinfunction "2_2") (pintype "passive"))
      (node (ref "JP6") (pin "10") (pinfunction "10_10") (pintype "passive"))
      (node (ref "U$1") (pin "17") (pinfunction "PE14/CSI-D10/LCD-D14_17") (pintype "bidirectional"))
      (node (ref "X3") (pin "4") (pinfunction "S_4") (pintype "passive"))
    )
    (net (code "21") (name "CSI_D11{slash}LCD_D15") (class "Default")
      (node (ref "J3") (pin "20") (pinfunction "MS_20") (pintype "passive"))
      (node (ref "JP10") (pin "9") (pinfunction "9_9") (pintype "passive"))
      (node (ref "JP11") (pin "1") (pinfunction "1_1") (pintype "passive"))
      (node (ref "JP6") (pin "9") (pinfunction "9_9") (pintype "passive"))
      (node (ref "U$1") (pin "16") (pinfunction "PE15/CSI-D11/LCD-D15_16") (pintype "bidirectional"))
      (node (ref "X3") (pin "5") (pinfunction "S_5") (pintype "passive"))
    )
    (net (code "22") (name "CSI_D12{slash}LCD_D18") (class "Default")
      (node (ref "J3") (pin "7") (pinfunction "MS_7") (pintype "passive"))
      (node (ref "JP12") (pin "15") (pinfunction "15_15") (pintype "passive"))
      (node (ref "U$1") (pin "15") (pinfunction "PE16/CSI-D12/LCD-D18_15") (pintype "bidirectional"))
      (node (ref "X3") (pin "22") (pinfunction "S_22") (pintype "passive"))
    )
    (net (code "23") (name "CSI_HSYNC{slash}LCD_HSYNC") (class "Default")
      (node (ref "J3") (pin "32") (pinfunction "MS_32") (pintype "passive"))
      (node (ref "JP10") (pin "6") (pinfunction "6_6") (pintype "passive"))
      (node (ref "JP11") (pin "14") (pinfunction "14_14") (pintype "passive"))
      (node (ref "JP6") (pin "6") (pinfunction "6_6") (pintype "passive"))
      (node (ref "U$1") (pin "35") (pinfunction "PE2/CSI-HSYNC/LCD-HSYNC_35") (pintype "bidirectional"))
      (node (ref "X3") (pin "17") (pinfunction "S_17") (pintype "passive"))
    )
    (net (code "24") (name "CSI_MCLK{slash}LCD_DE") (class "Default")
      (node (ref "J3") (pin "34") (pinfunction "MS_34") (pintype "passive"))
      (node (ref "JP10") (pin "8") (pinfunction "8_8") (pintype "passive"))
      (node (ref "JP11") (pin "15") (pinfunction "15_15") (pintype "passive"))
      (node (ref "JP6") (pin "8") (pinfunction "8_8") (pintype "passive"))
      (node (ref "U$1") (pin "36") (pinfunction "PE1/CSI-MCLK/LCD-DE_36") (pintype "bidirectional"))
      (node (ref "X3") (pin "20") (pinfunction "S_20") (pintype "passive"))
    )
    (net (code "25") (name "CSI_PCLK{slash}LCD_CLK") (class "Default")
      (node (ref "J3") (pin "30") (pinfunction "MS_30") (pintype "passive"))
      (node (ref "JP10") (pin "7") (pinfunction "7_7") (pintype "passive"))
      (node (ref "JP11") (pin "16") (pinfunction "16_16") (pintype "passive"))
      (node (ref "JP6") (pin "7") (pinfunction "7_7") (pintype "passive"))
      (node (ref "U$1") (pin "37") (pinfunction "PE0/CSI-CLK-/LCD-CLK_37") (pintype "bidirectional"))
      (node (ref "X3") (pin "21") (pinfunction "S_21") (pintype "passive"))
    )
    (net (code "26") (name "CSI_VSYNC{slash}LCD_VSYNC") (class "Default")
      (node (ref "J3") (pin "33") (pinfunction "MS_33") (pintype "passive"))
      (node (ref "JP10") (pin "5") (pinfunction "5_5") (pintype "passive"))
      (node (ref "JP11") (pin "13") (pinfunction "13_13") (pintype "passive"))
      (node (ref "JP6") (pin "5") (pinfunction "5_5") (pintype "passive"))
      (node (ref "U$1") (pin "34") (pinfunction "PE3/CSI-VSYNC/LCD-VSYNC_34") (pintype "bidirectional"))
      (node (ref "X3") (pin "16") (pinfunction "S_16") (pintype "passive"))
    )
    (net (code "27") (name "EPHY_RXN") (class "Default")
      (node (ref "R41") (pin "1") (pinfunction "1_1") (pintype "passive"))
      (node (ref "U$1") (pin "89") (pinfunction "EPHY_RXN_89") (pintype "bidirectional"))
      (node (ref "U$3") (pin "6") (pinfunction "RD-_6") (pintype "bidirectional"))
    )
    (net (code "28") (name "EPHY_RXP") (class "Default")
      (node (ref "R40") (pin "1") (pinfunction "1_1") (pintype "passive"))
      (node (ref "U$1") (pin "90") (pinfunction "EPHY_RXP_90") (pintype "bidirectional"))
      (node (ref "U$3") (pin "3") (pinfunction "RD+_3") (pintype "bidirectional"))
    )
    (net (code "29") (name "EPHY_TXN") (class "Default")
      (node (ref "R43") (pin "1") (pinfunction "1_1") (pintype "passive"))
      (node (ref "U$1") (pin "91") (pinfunction "EPHY_TXN_91") (pintype "bidirectional"))
      (node (ref "U$3") (pin "2") (pinfunction "TD-_2") (pintype "bidirectional"))
    )
    (net (code "30") (name "EPHY_TXP") (class "Default")
      (node (ref "R42") (pin "1") (pinfunction "1_1") (pintype "passive"))
      (node (ref "U$1") (pin "92") (pinfunction "EPHY_TXP_92") (pintype "bidirectional"))
      (node (ref "U$3") (pin "1") (pinfunction "TD+_1") (pintype "bidirectional"))
    )
    (net (code "31") (name "GND") (class "Default")
      (node (ref "ANT2") (pin "GND1") (pinfunction "GND1_GND1") (pintype "bidirectional"))
      (node (ref "ANT2") (pin "GND2") (pinfunction "GND2_GND2") (pintype "bidirectional"))
      (node (ref "C1") (pin "2") (pinfunction "2_2") (pintype "passive"))
      (node (ref "C10") (pin "2") (pinfunction "2_2") (pintype "passive"))
      (node (ref "C11") (pin "1") (pinfunction "1_1") (pintype "passive"))
      (node (ref "C12") (pin "1") (pinfunction "1_1") (pintype "passive"))
      (node (ref "C13") (pin "2") (pinfunction "2_2") (pintype "passive"))
      (node (ref "C15") (pin "1") (pinfunction "1_1") (pintype "passive"))
      (node (ref "C16") (pin "1") (pinfunction "1_1") (pintype "passive"))
      (node (ref "C17") (pin "2") (pinfunction "2_2") (pintype "passive"))
      (node (ref "C19") (pin "1") (pinfunction "1_1") (pintype "passive"))
      (node (ref "C2") (pin "2") (pinfunction "2_2") (pintype "passive"))
      (node (ref "C20") (pin "1") (pinfunction "1_1") (pintype "passive"))
      (node (ref "C21") (pin "1") (pinfunction "1_1") (pintype "passive"))
      (node (ref "C22") (pin "2") (pinfunction "2_2") (pintype "passive"))
      (node (ref "C23") (pin "1") (pinfunction "1_1") (pintype "passive"))
      (node (ref "C24") (pin "1") (pinfunction "1_1") (pintype "passive"))
      (node (ref "C26") (pin "1") (pinfunction "1_1") (pintype "passive"))
      (node (ref "C29") (pin "1") (pinfunction "1_1") (pintype "passive"))
      (node (ref "C3") (pin "2") (pinfunction "2_2") (pintype "passive"))
      (node (ref "C30") (pin "2") (pinfunction "2_2") (pintype "passive"))
      (node (ref "C31") (pin "2") (pinfunction "2_2") (pintype "passive"))
      (node (ref "C32") (pin "2") (pinfunction "2_2") (pintype "passive"))
      (node (ref "C33") (pin "2") (pinfunction "2_2") (pintype "passive"))
      (node (ref "C34") (pin "1") (pinfunction "1_1") (pintype "passive"))
      (node (ref "C35") (pin "2") (pinfunction "2_2") (pintype "passive"))
      (node (ref "C36") (pin "2") (pinfunction "2_2") (pintype "passive"))
      (node (ref "C37") (pin "2") (pinfunction "2_2") (pintype "passive"))
      (node (ref "C38") (pin "1") (pinfunction "1_1") (pintype "passive"))
      (node (ref "C39") (pin "2") (pinfunction "2_2") (pintype "passive"))
      (node (ref "C40") (pin "2") (pinfunction "2_2") (pintype "passive"))
      (node (ref "C43") (pin "1") (pinfunction "1_1") (pintype "passive"))
      (node (ref "C44") (pin "1") (pinfunction "1_1") (pintype "passive"))
      (node (ref "C46") (pin "1") (pinfunction "1_1") (pintype "passive"))
      (node (ref "C47") (pin "2") (pinfunction "2_2") (pintype "passive"))
      (node (ref "C48") (pin "2") (pinfunction "2_2") (pintype "passive"))
      (node (ref "C49") (pin "2") (pinfunction "2_2") (pintype "passive"))
      (node (ref "C5") (pin "2") (pinfunction "2_2") (pintype "passive"))
      (node (ref "C50") (pin "2") (pinfunction "2_2") (pintype "passive"))
      (node (ref "C51") (pin "2") (pinfunction "2_2") (pintype "passive"))
      (node (ref "C52") (pin "2") (pinfunction "2_2") (pintype "passive"))
      (node (ref "C53") (pin "2") (pinfunction "2_2") (pintype "passive"))
      (node (ref "C54") (pin "2") (pinfunction "2_2") (pintype "passive"))
      (node (ref "C55") (pin "2") (pinfunction "2_2") (pintype "passive"))
      (node (ref "C56") (pin "2") (pinfunction "2_2") (pintype "passive"))
      (node (ref "C57") (pin "2") (pinfunction "2_2") (pintype "passive"))
      (node (ref "C58") (pin "2") (pinfunction "2_2") (pintype "passive"))
      (node (ref "C59") (pin "2") (pinfunction "2_2") (pintype "passive"))
      (node (ref "C6") (pin "2") (pinfunction "2_2") (pintype "passive"))
      (node (ref "C60") (pin "2") (pinfunction "2_2") (pintype "passive"))
      (node (ref "C61") (pin "2") (pinfunction "2_2") (pintype "passive"))
      (node (ref "C62") (pin "2") (pinfunction "2_2") (pintype "passive"))
      (node (ref "C63") (pin "2") (pinfunction "2_2") (pintype "passive"))
      (node (ref "C64") (pin "2") (pinfunction "2_2") (pintype "passive"))
      (node (ref "C65") (pin "2") (pinfunction "2_2") (pintype "passive"))
      (node (ref "C66") (pin "2") (pinfunction "2_2") (pintype "passive"))
      (node (ref "C67") (pin "2") (pinfunction "2_2") (pintype "passive"))
      (node (ref "C68") (pin "2") (pinfunction "2_2") (pintype "passive"))
      (node (ref "C69") (pin "2") (pinfunction "2_2") (pintype "passive"))
      (node (ref "C7") (pin "2") (pinfunction "2_2") (pintype "passive"))
      (node (ref "C70") (pin "2") (pinfunction "2_2") (pintype "passive"))
      (node (ref "C71") (pin "2") (pinfunction "2_2") (pintype "passive"))
      (node (ref "C72") (pin "2") (pinfunction "2_2") (pintype "passive"))
      (node (ref "C73") (pin "2") (pinfunction "2_2") (pintype "passive"))
      (node (ref "C74") (pin "2") (pinfunction "2_2") (pintype "passive"))
      (node (ref "C75") (pin "2") (pinfunction "2_2") (pintype "passive"))
      (node (ref "C76") (pin "2") (pinfunction "2_2") (pintype "passive"))
      (node (ref "C8") (pin "2") (pinfunction "2_2") (pintype "passive"))
      (node (ref "C9") (pin "2") (pinfunction "2_2") (pintype "passive"))
      (node (ref "CN2") (pin "GND") (pinfunction "GND_GND") (pintype "power_in"))
      (node (ref "CN2") (pin "GNDBREAK") (pinfunction "GNDBREAK_GNDBREAK") (pintype "power_in"))
      (node (ref "IC1") (pin "1") (pinfunction "GND_1") (pintype "input"))
      (node (ref "J1") (pin "6") (pinfunction "GND_6") (pintype "power_in"))
      (node (ref "J1") (pin "S1") (pinfunction "S_S1") (pintype "passive"))
      (node (ref "J1") (pin "S2") (pinfunction "S_S2") (pintype "passive"))
      (node (ref "J1") (pin "S3") (pinfunction "S_S3") (pintype "passive"))
      (node (ref "J1") (pin "S4") (pinfunction "S_S4") (pintype "passive"))
      (node (ref "J3") (pin "13") (pinfunction "MS_13") (pintype "passive"))
      (node (ref "J3") (pin "14") (pinfunction "MS_14") (pintype "passive"))
      (node (ref "J3") (pin "21") (pinfunction "MS_21") (pintype "passive"))
      (node (ref "J3") (pin "22") (pinfunction "MS_22") (pintype "passive"))
      (node (ref "J3") (pin "29") (pinfunction "MS_29") (pintype "passive"))
      (node (ref "J3") (pin "3") (pinfunction "MS_3") (pintype "passive"))
      (node (ref "J3") (pin "36") (pinfunction "MS_36") (pintype "passive"))
      (node (ref "J3") (pin "5") (pinfunction "MS_5") (pintype "passive"))
      (node (ref "J3") (pin "6") (pinfunction "MS_6") (pintype "passive"))
      (node (ref "J4") (pin "12") (pinfunction "4_12") (pintype "passive"))
      (node (ref "J4") (pin "15") (pinfunction "1_15") (pintype "passive"))
      (node (ref "J4") (pin "6") (pinfunction "10_6") (pintype "passive"))
      (node (ref "J4") (pin "9") (pinfunction "7_9") (pintype "passive"))
      (node (ref "JP1") (pin "14") (pinfunction "14_14") (pintype "passive"))
      (node (ref "JP1") (pin "20") (pinfunction "20_20") (pintype "passive"))
      (node (ref "JP1") (pin "25") (pinfunction "25_25") (pintype "passive"))
      (node (ref "JP1") (pin "6") (pinfunction "6_6") (pintype "passive"))
      (node (ref "JP1") (pin "9") (pinfunction "9_9") (pintype "passive"))
      (node (ref "JP10") (pin "18") (pinfunction "18_18") (pintype "passive"))
      (node (ref "JP10") (pin "2") (pinfunction "2_2") (pintype "passive"))
      (node (ref "JP12") (pin "1") (pinfunction "1_1") (pintype "passive"))
      (node (ref "JP12") (pin "16") (pinfunction "16_16") (pintype "passive"))
      (node (ref "JP12") (pin "2") (pinfunction "2_2") (pintype "passive"))
      (node (ref "JP12") (pin "3") (pinfunction "3_3") (pintype "passive"))
      (node (ref "JP5") (pin "3") (pinfunction "3_3") (pintype "passive"))
      (node (ref "JP6") (pin "18") (pinfunction "18_18") (pintype "passive"))
      (node (ref "JP6") (pin "2") (pinfunction "2_2") (pintype "passive"))
      (node (ref "LED1") (pin "C") (pinfunction "C_C") (pintype "passive"))
      (node (ref "LED2") (pin "C") (pinfunction "C_C") (pintype "passive"))
      (node (ref "R12") (pin "2") (pinfunction "2_2") (pintype "passive"))
      (node (ref "R14") (pin "1") (pinfunction "1_1") (pintype "passive"))
      (node (ref "R15") (pin "1") (pinfunction "1_1") (pintype "passive"))
      (node (ref "R24") (pin "2") (pinfunction "2_2") (pintype "passive"))
      (node (ref "R27") (pin "1") (pinfunction "1_1") (pintype "passive"))
      (node (ref "R28") (pin "2") (pinfunction "2_2") (pintype "passive"))
      (node (ref "R47") (pin "2") (pinfunction "2_2") (pintype "passive"))
      (node (ref "R54") (pin "1") (pinfunction "1_1") (pintype "passive"))
      (node (ref "R56") (pin "1") (pinfunction "1_1") (pintype "passive"))
      (node (ref "R58") (pin "1") (pinfunction "1_1") (pintype "passive"))
      (node (ref "S1") (pin "1") (pinfunction "1_1") (pintype "passive"))
      (node (ref "S2") (pin "1") (pinfunction "1_1") (pintype "passive"))
      (node (ref "S3") (pin "1") (pinfunction "1_1") (pintype "passive"))
      (node (ref "S4") (pin "1") (pinfunction "1_1") (pintype "passive"))
      (node (ref "S5") (pin "1") (pinfunction "1_1") (pintype "passive"))
      (node (ref "U$1") (pin "116") (pinfunction "AGND_116") (pintype "bidirectional"))
      (node (ref "U$1") (pin "P$1") (pinfunction "PAD_P$1") (pintype "bidirectional"))
      (node (ref "U$2") (pin "P$1") (pinfunction "GND1_P$1") (pintype "bidirectional"))
      (node (ref "U$2") (pin "P$20") (pinfunction "GND20_P$20") (pintype "bidirectional"))
      (node (ref "U$2") (pin "P$3") (pinfunction "GND3_P$3") (pintype "bidirectional"))
      (node (ref "U$2") (pin "P$31") (pinfunction "GND31_P$31") (pintype "bidirectional"))
      (node (ref "U$2") (pin "P$33") (pinfunction "GND33_P$33") (pintype "bidirectional"))
      (node (ref "U$2") (pin "P$36") (pinfunction "GND36_P$36") (pintype "bidirectional"))
      (node (ref "U$2") (pin "P$41") (pinfunction "UART_RTS_P$41") (pintype "bidirectional"))
      (node (ref "U$3") (pin "10") (pinfunction "G-_10") (pintype "bidirectional"))
      (node (ref "U$3") (pin "11") (pinfunction "Y-_11") (pintype "bidirectional"))
      (node (ref "U$3") (pin "8") (pinfunction "GND_8") (pintype "bidirectional"))
      (node (ref "U$3") (pin "SHIELD1") (pinfunction "SHIELD0_SHIELD1") (pintype "bidirectional"))
      (node (ref "U$3") (pin "SHIELD2") (pinfunction "SHIELD1_SHIELD2") (pintype "bidirectional"))
      (node (ref "U$4") (pin "1") (pinfunction "GND3_1") (pintype "bidirectional"))
      (node (ref "U$4") (pin "12") (pinfunction "GND1_12") (pintype "bidirectional"))
      (node (ref "U$4") (pin "13") (pinfunction "GND1_13") (pintype "bidirectional"))
      (node (ref "U$4") (pin "15") (pinfunction "AGND_15") (pintype "bidirectional"))
      (node (ref "U$4") (pin "17") (pinfunction "AGND_17") (pintype "bidirectional"))
      (node (ref "U$4") (pin "21") (pinfunction "PAD_21") (pintype "bidirectional"))
      (node (ref "U$4") (pin "4") (pinfunction "GND2_4") (pintype "bidirectional"))
      (node (ref "U$4") (pin "5") (pinfunction "GND2_5") (pintype "bidirectional"))
      (node (ref "U$5") (pin "5") (pinfunction "5_5") (pintype "input"))
      (node (ref "U$5") (pin "M1") (pinfunction "S1_M1") (pintype "passive"))
      (node (ref "U$5") (pin "M2") (pinfunction "S2_M2") (pintype "passive"))
      (node (ref "U$5") (pin "M3") (pinfunction "S3_M3") (pintype "passive"))
      (node (ref "U$5") (pin "M4") (pinfunction "S4_M4") (pintype "passive"))
      (node (ref "U$6") (pin "2") (pinfunction "VSS_2") (pintype "bidirectional"))
      (node (ref "U$7") (pin "1") (pinfunction "G_1") (pintype "passive"))
      (node (ref "U$8") (pin "6") (pinfunction "GND_6") (pintype "bidirectional"))
      (node (ref "U$8") (pin "8") (pinfunction "A0_8") (pintype "bidirectional"))
      (node (ref "U$9") (pin "2") (pinfunction "GND_2") (pintype "bidirectional"))
      (node (ref "U1") (pin "4") (pinfunction "GND_4") (pintype "power_in"))
      (node (ref "X1") (pin "GND") (pinfunction "GND_GND") (pintype "bidirectional"))
      (node (ref "X3") (pin "3") (pinfunction "S_3") (pintype "passive"))
    )
    (net (code "32") (name "HP_COM") (class "Default")
      (node (ref "C18") (pin "2") (pinfunction "2_2") (pintype "passive"))
      (node (ref "J2") (pin "RING2") (pinfunction "RING2_RING2") (pintype "bidirectional"))
      (node (ref "R26") (pin "2") (pinfunction "2_2") (pintype "passive"))
      (node (ref "U$1") (pin "125") (pinfunction "HPCOM_125") (pintype "bidirectional"))
    )
    (net (code "33") (name "HP_COMFB") (class "Default")
      (node (ref "R26") (pin "1") (pinfunction "1_1") (pintype "passive"))
      (node (ref "U$1") (pin "124") (pinfunction "HPCOMFB_124") (pintype "bidirectional"))
    )
    (net (code "34") (name "HP_L") (class "Default")
      (node (ref "J2") (pin "TIP") (pinfunction "TIP_TIP") (pintype "bidirectional"))
      (node (ref "U$1") (pin "121") (pinfunction "HPOUTL_121") (pintype "bidirectional"))
    )
    (net (code "35") (name "HP_R") (class "Default")
      (node (ref "J2") (pin "RING1") (pinfunction "RING1_RING1") (pintype "bidirectional"))
      (node (ref "U$1") (pin "120") (pinfunction "HPOUTR_120") (pintype "bidirectional"))
    )
    (net (code "36") (name "I2C0{slash}SCL") (class "Default")
      (node (ref "JP1") (pin "5") (pinfunction "5_5") (pintype "passive"))
      (node (ref "U$1") (pin "45") (pinfunction "PB6/I2C0/SCL_45") (pintype "bidirectional"))
    )
    (net (code "37") (name "I2C0{slash}SDA") (class "Default")
      (node (ref "JP1") (pin "3") (pinfunction "3_3") (pintype "passive"))
      (node (ref "U$1") (pin "46") (pinfunction "PB7/I2C0/SDA_46") (pintype "bidirectional"))
    )
    (net (code "38") (name "I2C1{slash}SCL") (class "Default")
      (node (ref "J4") (pin "3") (pinfunction "13_3") (pintype "passive"))
      (node (ref "JP1") (pin "26") (pinfunction "26_26") (pintype "passive"))
      (node (ref "JP10") (pin "3") (pinfunction "3_3") (pintype "passive"))
      (node (ref "JP12") (pin "11") (pinfunction "11_11") (pintype "passive"))
      (node (ref "JP6") (pin "3") (pinfunction "3_3") (pintype "passive"))
      (node (ref "R38") (pin "2") (pinfunction "2_2") (pintype "passive"))
      (node (ref "R44") (pin "2") (pinfunction "2_2") (pintype "passive"))
      (node (ref "U$1") (pin "9") (pinfunction "PE21/UART1/TX_9") (pintype "bidirectional"))
      (node (ref "U$8") (pin "10") (pinfunction "SCL_10") (pintype "bidirectional"))
      (node (ref "X3") (pin "19") (pinfunction "S_19") (pintype "passive"))
    )
    (net (code "39") (name "I2C1{slash}SDA") (class "Default")
      (node (ref "J4") (pin "2") (pinfunction "14_2") (pintype "passive"))
      (node (ref "JP1") (pin "22") (pinfunction "22_22") (pintype "passive"))
      (node (ref "JP10") (pin "4") (pinfunction "4_4") (pintype "passive"))
      (node (ref "JP12") (pin "10") (pinfunction "10_10") (pintype "passive"))
      (node (ref "JP6") (pin "4") (pinfunction "4_4") (pintype "passive"))
      (node (ref "R39") (pin "2") (pinfunction "2_2") (pintype "passive"))
      (node (ref "R45") (pin "2") (pinfunction "2_2") (pintype "passive"))
      (node (ref "U$1") (pin "8") (pinfunction "PE22/UART1/RX_8") (pintype "bidirectional"))
      (node (ref "U$8") (pin "9") (pinfunction "SDA_9") (pintype "bidirectional"))
      (node (ref "X3") (pin "18") (pinfunction "S_18") (pintype "passive"))
    )
    (net (code "40") (name "KEYADC0") (class "Default")
      (node (ref "C34") (pin "2") (pinfunction "2_2") (pintype "passive"))
      (node (ref "R20") (pin "2") (pinfunction "2_2") (pintype "passive"))
      (node (ref "R29") (pin "1") (pinfunction "1_1") (pintype "passive"))
      (node (ref "U$1") (pin "112") (pinfunction "LRADC0_112") (pintype "bidirectional"))
    )
    (net (code "41") (name "LCD_D19") (class "Default")
      (node (ref "J3") (pin "8") (pinfunction "MS_8") (pintype "passive"))
      (node (ref "JP12") (pin "14") (pinfunction "14_14") (pintype "passive"))
      (node (ref "U$1") (pin "14") (pinfunction "PE17/CSI-D13/LCD-D19_14") (pintype "bidirectional"))
    )
    (net (code "42") (name "LCD_D20") (class "Default")
      (node (ref "J3") (pin "9") (pinfunction "MS_9") (pintype "passive"))
      (node (ref "JP12") (pin "13") (pinfunction "13_13") (pintype "passive"))
      (node (ref "U$1") (pin "13") (pinfunction "PE18/CSI-D14/LCD-D20_13") (pintype "bidirectional"))
    )
    (net (code "43") (name "LCD_D21") (class "Default")
      (node (ref "J3") (pin "10") (pinfunction "MS_10") (pintype "passive"))
      (node (ref "JP12") (pin "12") (pinfunction "12_12") (pintype "passive"))
      (node (ref "U$1") (pin "11") (pinfunction "PE19/CSI-D15/LCD-D21_11") (pintype "bidirectional"))
    )
    (net (code "44") (name "LCD_D22") (class "Default")
      (node (ref "J3") (pin "11") (pinfunction "MS_11") (pintype "passive"))
      (node (ref "JP12") (pin "9") (pinfunction "9_9") (pintype "passive"))
      (node (ref "U$1") (pin "7") (pinfunction "PE23/LCD-D22/_7") (pintype "bidirectional"))
    )
    (net (code "45") (name "LCD_D23") (class "Default")
      (node (ref "J3") (pin "12") (pinfunction "MS_12") (pintype "passive"))
      (node (ref "JP12") (pin "8") (pinfunction "8_8") (pintype "passive"))
      (node (ref "U$1") (pin "6") (pinfunction "PE24/LCD-D23_6") (pintype "bidirectional"))
    )
    (net (code "46") (name "LINK_LED") (class "Default")
      (node (ref "R53") (pin "1") (pinfunction "1_1") (pintype "passive"))
      (node (ref "U$1") (pin "77") (pinfunction "EPHY_LINK_LED_77") (pintype "bidirectional"))
    )
    (net (code "47") (name "MCSI-CKN") (class "Default")
      (node (ref "J4") (pin "8") (pinfunction "8_8") (pintype "passive"))
      (node (ref "U$1") (pin "87") (pinfunction "MCSI-CKN_87") (pintype "bidirectional"))
    )
    (net (code "48") (name "MCSI-CKP") (class "Default")
      (node (ref "J4") (pin "7") (pinfunction "9_7") (pintype "passive"))
      (node (ref "U$1") (pin "86") (pinfunction "MCSI-CKP_86") (pintype "bidirectional"))
    )
    (net (code "49") (name "MCSI-D0N") (class "Default")
      (node (ref "J4") (pin "14") (pinfunction "2_14") (pintype "passive"))
      (node (ref "U$1") (pin "82") (pinfunction "MCSI-D0N_82") (pintype "bidirectional"))
    )
    (net (code "50") (name "MCSI-D0P") (class "Default")
      (node (ref "J4") (pin "13") (pinfunction "3_13") (pintype "passive"))
      (node (ref "U$1") (pin "81") (pinfunction "MCSI-D0P_81") (pintype "bidirectional"))
    )
    (net (code "51") (name "MCSI-D1N") (class "Default")
      (node (ref "J4") (pin "11") (pinfunction "5_11") (pintype "passive"))
      (node (ref "U$1") (pin "84") (pinfunction "MCSI-D1N_84") (pintype "bidirectional"))
    )
    (net (code "52") (name "MCSI-D1P") (class "Default")
      (node (ref "J4") (pin "10") (pinfunction "6_10") (pintype "passive"))
      (node (ref "U$1") (pin "83") (pinfunction "MCSI-D1P_83") (pintype "bidirectional"))
    )
    (net (code "53") (name "MICIN1N") (class "Default")
      (node (ref "C28") (pin "1") (pinfunction "1_1") (pintype "passive"))
      (node (ref "U$1") (pin "114") (pinfunction "MICIN1N_114") (pintype "bidirectional"))
    )
    (net (code "54") (name "MICIN1P") (class "Default")
      (node (ref "C27") (pin "1") (pinfunction "1_1") (pintype "passive"))
      (node (ref "U$1") (pin "113") (pinfunction "MICIN1P_113") (pintype "bidirectional"))
    )
    (net (code "55") (name "MIC_HBIAS") (class "Default")
      (node (ref "C17") (pin "1") (pinfunction "1_1") (pintype "passive"))
      (node (ref "R25") (pin "2") (pinfunction "2_2") (pintype "passive"))
      (node (ref "U$1") (pin "119") (pinfunction "HBIAS_119") (pintype "bidirectional"))
    )
    (net (code "56") (name "MIPI-CSI-MCLK") (class "Default")
      (node (ref "J4") (pin "5") (pinfunction "11_5") (pintype "passive"))
      (node (ref "JP1") (pin "15") (pinfunction "15_15") (pintype "passive"))
      (node (ref "U$1") (pin "10") (pinfunction "PE20/CSI-FIELD/CSI-MIPI-M-CLK_10") (pintype "bidirectional"))
    )
    (net (code "57") (name "Net-(ANT2-PadD)") (class "Default")
      (node (ref "ANT2") (pin "D") (pinfunction "D_D") (pintype "bidirectional"))
      (node (ref "C4") (pin "2") (pinfunction "2_2") (pintype "passive"))
    )
    (net (code "58") (name "Net-(C18-Pad1)") (class "Default")
      (node (ref "C18") (pin "1") (pinfunction "1_1") (pintype "passive"))
      (node (ref "R15") (pin "2") (pinfunction "2_2") (pintype "passive"))
    )
    (net (code "59") (name "Net-(C23-Pad2)") (class "Default")
      (node (ref "C23") (pin "2") (pinfunction "2_2") (pintype "passive"))
      (node (ref "C25") (pin "2") (pinfunction "2_2") (pintype "passive"))
      (node (ref "C27") (pin "2") (pinfunction "2_2") (pintype "passive"))
      (node (ref "MIC") (pin "2") (pinfunction "2_2") (pintype "passive"))
      (node (ref "R30") (pin "1") (pinfunction "1_1") (pintype "passive"))
    )
    (net (code "60") (name "Net-(C24-Pad2)") (class "Default")
      (node (ref "C24") (pin "2") (pinfunction "2_2") (pintype "passive"))
      (node (ref "C25") (pin "1") (pinfunction "1_1") (pintype "passive"))
      (node (ref "C28") (pin "2") (pinfunction "2_2") (pintype "passive"))
      (node (ref "MIC") (pin "1") (pinfunction "1_1") (pintype "passive"))
      (node (ref "R28") (pin "1") (pinfunction "1_1") (pintype "passive"))
    )
    (net (code "61") (name "Net-(CN2-PadPWR)") (class "Default")
      (node (ref "CN2") (pin "PWR") (pinfunction "PWR_PWR") (pintype "power_in"))
      (node (ref "F1") (pin "1") (pinfunction "1_1") (pintype "passive"))
    )
    (net (code "62") (name "Net-(J2-PadEARTH)") (class "Default")
      (node (ref "J2") (pin "EARTH") (pinfunction "EARTH_EARTH") (pintype "bidirectional"))
      (node (ref "R25") (pin "1") (pinfunction "1_1") (pintype "passive"))
    )
    (net (code "63") (name "Net-(J3AC-MS)") (class "Default")
      (node (ref "J3") (pin "35") (pinfunction "MS_35") (pintype "passive"))
      (node (ref "R4") (pin "1") (pinfunction "1_1") (pintype "passive"))
    )
    (net (code "64") (name "Net-(L1-2)") (class "Default")
      (node (ref "D1") (pin "A") (pinfunction "A_A") (pintype "passive"))
      (node (ref "L1") (pin "P$2") (pinfunction "2_P$2") (pintype "passive"))
      (node (ref "U$9") (pin "1") (pinfunction "SW_1") (pintype "bidirectional"))
    )
    (net (code "65") (name "Net-(L3-2)") (class "Default")
      (node (ref "L3") (pin "P$2") (pinfunction "2_P$2") (pintype "passive"))
      (node (ref "U$4") (pin "11") (pinfunction "LX1_11") (pintype "bidirectional"))
    )
    (net (code "66") (name "Net-(L4-2)") (class "Default")
      (node (ref "L4") (pin "P$2") (pinfunction "2_P$2") (pintype "passive"))
      (node (ref "U$4") (pin "6") (pinfunction "LX2_6") (pintype "bidirectional"))
    )
    (net (code "67") (name "Net-(L5-2)") (class "Default")
      (node (ref "L5") (pin "P$2") (pinfunction "2_P$2") (pintype "passive"))
      (node (ref "U$4") (pin "20") (pinfunction "LX3_20") (pintype "bidirectional"))
    )
    (net (code "68") (name "Net-(LED1-PadA)") (class "Default")
      (node (ref "LED1") (pin "A") (pinfunction "A_A") (pintype "passive"))
      (node (ref "R16") (pin "1") (pinfunction "1_1") (pintype "passive"))
    )
    (net (code "69") (name "Net-(LED2-PadA)") (class "Default")
      (node (ref "LED2") (pin "A") (pinfunction "A_A") (pintype "passive"))
      (node (ref "R17") (pin "1") (pinfunction "1_1") (pintype "passive"))
    )
    (net (code "70") (name "Net-(R20-Pad1)") (class "Default")
      (node (ref "R20") (pin "1") (pinfunction "1_1") (pintype "passive"))
      (node (ref "R21") (pin "2") (pinfunction "2_2") (pintype "passive"))
      (node (ref "S1") (pin "2") (pinfunction "2_2") (pintype "passive"))
    )
    (net (code "71") (name "Net-(R21-Pad1)") (class "Default")
      (node (ref "R21") (pin "1") (pinfunction "1_1") (pintype "passive"))
      (node (ref "R22") (pin "2") (pinfunction "2_2") (pintype "passive"))
      (node (ref "S2") (pin "2") (pinfunction "2_2") (pintype "passive"))
    )
    (net (code "72") (name "Net-(R22-Pad1)") (class "Default")
      (node (ref "R22") (pin "1") (pinfunction "1_1") (pintype "passive"))
      (node (ref "R23") (pin "2") (pinfunction "2_2") (pintype "passive"))
      (node (ref "S3") (pin "2") (pinfunction "2_2") (pintype "passive"))
    )
    (net (code "73") (name "Net-(R23-Pad1)") (class "Default")
      (node (ref "R23") (pin "1") (pinfunction "1_1") (pintype "passive"))
      (node (ref "S4") (pin "2") (pinfunction "2_2") (pintype "passive"))
    )
    (net (code "74") (name "Net-(U$1A-HPVCCBP)") (class "Default")
      (node (ref "C22") (pin "1") (pinfunction "1_1") (pintype "passive"))
      (node (ref "C29") (pin "2") (pinfunction "2_2") (pintype "passive"))
      (node (ref "U$1") (pin "123") (pinfunction "HPVCCBP_123") (pintype "bidirectional"))
    )
    (net (code "75") (name "Net-(U$1D-RESET)") (class "Default")
      (node (ref "C13") (pin "1") (pinfunction "1_1") (pintype "passive"))
      (node (ref "R11") (pin "1") (pinfunction "1_1") (pintype "passive"))
      (node (ref "S5") (pin "2") (pinfunction "2_2") (pintype "passive"))
      (node (ref "U$1") (pin "99") (pinfunction "RESET_99") (pintype "bidirectional"))
    )
    (net (code "76") (name "Net-(U$1D-X24MIN)") (class "Default")
      (node (ref "C12") (pin "2") (pinfunction "2_2") (pintype "passive"))
      (node (ref "Q1") (pin "2") (pinfunction "2_2") (pintype "passive"))
      (node (ref "U$1") (pin "75") (pinfunction "X24MIN_75") (pintype "bidirectional"))
    )
    (net (code "77") (name "Net-(U$1D-X24MOUNT)") (class "Default")
      (node (ref "C11") (pin "2") (pinfunction "2_2") (pintype "passive"))
      (node (ref "Q1") (pin "1") (pinfunction "1_1") (pintype "passive"))
      (node (ref "U$1") (pin "74") (pinfunction "X24MOUNT_74") (pintype "bidirectional"))
    )
    (net (code "78") (name "Net-(U$1D-X32KIN)") (class "Default")
      (node (ref "C8") (pin "1") (pinfunction "1_1") (pintype "passive"))
      (node (ref "Q2") (pin "1") (pinfunction "1_1") (pintype "passive"))
      (node (ref "R3") (pin "2") (pinfunction "2_2") (pintype "passive"))
      (node (ref "U$1") (pin "96") (pinfunction "X32KIN_96") (pintype "bidirectional"))
    )
    (net (code "79") (name "Net-(U$1D-X32KOUT)") (class "Default")
      (node (ref "C10") (pin "1") (pinfunction "1_1") (pintype "passive"))
      (node (ref "Q2") (pin "2") (pinfunction "2_2") (pintype "passive"))
      (node (ref "R3") (pin "1") (pinfunction "1_1") (pintype "passive"))
      (node (ref "U$1") (pin "95") (pinfunction "X32KOUT_95") (pintype "bidirectional"))
    )
    (net (code "80") (name "Net-(U$1E-EPHY_RTX)") (class "Default")
      (node (ref "R24") (pin "1") (pinfunction "1_1") (pintype "passive"))
      (node (ref "U$1") (pin "94") (pinfunction "EPHY_RTX_94") (pintype "bidirectional"))
    )
    (net (code "81") (name "Net-(U$1F-RTC-VIO)") (class "Default")
      (node (ref "C7") (pin "1") (pinfunction "1_1") (pintype "passive"))
      (node (ref "U$1") (pin "97") (pinfunction "RTC-VIO_97") (pintype "bidirectional"))
    )
    (net (code "82") (name "Net-(U$1F-VCC-RTC)") (class "Default")
      (node (ref "JP5") (pin "2") (pinfunction "2_2") (pintype "passive"))
      (node (ref "U$1") (pin "98") (pinfunction "VCC-RTC_98") (pintype "bidirectional"))
    )
    (net (code "83") (name "Net-(U$1G-SZQ)") (class "Default")
      (node (ref "R12") (pin "1") (pinfunction "1_1") (pintype "passive"))
      (node (ref "U$1") (pin "73") (pinfunction "SZQ_73") (pintype "bidirectional"))
    )
    (net (code "84") (name "Net-(U$2-BT_RST)") (class "Default")
      (node (ref "R10") (pin "1") (pinfunction "1_1") (pintype "passive"))
      (node (ref "U$2") (pin "P$34") (pinfunction "BT_RST_P$34") (pintype "bidirectional"))
    )
    (net (code "85") (name "Net-(U$2-UART_CTS)") (class "Default")
      (node (ref "JP7") (pin "3") (pinfunction "3_3") (pintype "passive"))
      (node (ref "U$2") (pin "P$44") (pinfunction "UART_CTS_P$44") (pintype "bidirectional"))
    )
    (net (code "86") (name "Net-(U$2-UART_RXD)") (class "Default")
      (node (ref "JP7") (pin "2") (pinfunction "2_2") (pintype "passive"))
      (node (ref "U$2") (pin "P$43") (pinfunction "UART_RXD_P$43") (pintype "bidirectional"))
    )
    (net (code "87") (name "Net-(U$2-UART_TXD)") (class "Default")
      (node (ref "JP7") (pin "1") (pinfunction "1_1") (pintype "passive"))
      (node (ref "U$2") (pin "P$42") (pinfunction "UART_TXD_P$42") (pintype "bidirectional"))
    )
    (net (code "88") (name "Net-(U$2-VIN_LDO)") (class "Default")
      (node (ref "R19") (pin "1") (pinfunction "1_1") (pintype "passive"))
      (node (ref "U$2") (pin "P$23") (pinfunction "VIN_LDO_P$23") (pintype "bidirectional"))
    )
    (net (code "89") (name "Net-(U$2-WL_BT_ANT)") (class "Default")
      (node (ref "C4") (pin "1") (pinfunction "1_1") (pintype "passive"))
      (node (ref "U$2") (pin "P$2") (pinfunction "WL_BT_ANT_P$2") (pintype "bidirectional"))
    )
    (net (code "90") (name "Net-(U$2-WL_REG)") (class "Default")
      (node (ref "R9") (pin "2") (pinfunction "2_2") (pintype "passive"))
      (node (ref "U$2") (pin "P$12") (pinfunction "WL_REG_P$12") (pintype "bidirectional"))
    )
    (net (code "91") (name "Net-(U$3-G+)") (class "Default")
      (node (ref "R53") (pin "2") (pinfunction "2_2") (pintype "passive"))
      (node (ref "U$3") (pin "9") (pinfunction "G+_9") (pintype "bidirectional"))
    )
    (net (code "92") (name "Net-(U$3-P4)") (class "Default")
      (node (ref "C49") (pin "1") (pinfunction "1_1") (pintype "passive"))
      (node (ref "L2") (pin "2") (pinfunction "2_2") (pintype "passive"))
      (node (ref "R42") (pin "2") (pinfunction "2_2") (pintype "passive"))
      (node (ref "R43") (pin "2") (pinfunction "2_2") (pintype "passive"))
      (node (ref "U$3") (pin "4") (pinfunction "P4_4") (pintype "bidirectional"))
    )
    (net (code "93") (name "Net-(U$3-P5)") (class "Default")
      (node (ref "C48") (pin "1") (pinfunction "1_1") (pintype "passive"))
      (node (ref "R40") (pin "2") (pinfunction "2_2") (pintype "passive"))
      (node (ref "R41") (pin "2") (pinfunction "2_2") (pintype "passive"))
      (node (ref "U$3") (pin "5") (pinfunction "P5_5") (pintype "bidirectional"))
    )
    (net (code "94") (name "Net-(U$3-Y+)") (class "Default")
      (node (ref "R52") (pin "2") (pinfunction "2_2") (pintype "passive"))
      (node (ref "U$3") (pin "12") (pinfunction "Y+_12") (pintype "bidirectional"))
    )
    (net (code "95") (name "Net-(U$4-FB1)") (class "Default")
      (node (ref "C41") (pin "2") (pinfunction "2_2") (pintype "passive"))
      (node (ref "R54") (pin "2") (pinfunction "2_2") (pintype "passive"))
      (node (ref "R7") (pin "2") (pinfunction "2_2") (pintype "passive"))
      (node (ref "U$4") (pin "14") (pinfunction "FB1_14") (pintype "bidirectional"))
    )
    (net (code "96") (name "Net-(U$4-FB2)") (class "Default")
      (node (ref "C42") (pin "2") (pinfunction "2_2") (pintype "passive"))
      (node (ref "R55") (pin "2") (pinfunction "2_2") (pintype "passive"))
      (node (ref "R56") (pin "2") (pinfunction "2_2") (pintype "passive"))
      (node (ref "U$4") (pin "3") (pinfunction "FB2_3") (pintype "bidirectional"))
    )
    (net (code "97") (name "Net-(U$4-FB3)") (class "Default")
      (node (ref "C45") (pin "2") (pinfunction "2_2") (pintype "passive"))
      (node (ref "R57") (pin "2") (pinfunction "2_2") (pintype "passive"))
      (node (ref "R58") (pin "2") (pinfunction "2_2") (pintype "passive"))
      (node (ref "U$4") (pin "2") (pinfunction "FB3_2") (pintype "bidirectional"))
    )
    (net (code "98") (name "Net-(U$7-D)") (class "Default")
      (node (ref "F1") (pin "2") (pinfunction "2_2") (pintype "passive"))
      (node (ref "U$7") (pin "3") (pinfunction "D_3") (pintype "passive"))
    )
    (net (code "99") (name "PB2") (class "Default")
      (node (ref "JP1") (pin "12") (pinfunction "12_12") (pintype "passive"))
      (node (ref "R17") (pin "2") (pinfunction "2_2") (pintype "passive"))
      (node (ref "U$1") (pin "41") (pinfunction "PB2_41") (pintype "bidirectional"))
    )
    (net (code "100") (name "PB3") (class "Default")
      (node (ref "J4") (pin "4") (pinfunction "12_4") (pintype "passive"))
      (node (ref "JP1") (pin "7") (pinfunction "7_7") (pintype "passive"))
      (node (ref "U$1") (pin "42") (pinfunction "PB3_42") (pintype "bidirectional"))
    )
    (net (code "101") (name "PB4{slash}PWM0") (class "Default")
      (node (ref "JP1") (pin "13") (pinfunction "13_13") (pintype "passive"))
      (node (ref "U$1") (pin "43") (pinfunction "PB4/PWM0_43") (pintype "bidirectional"))
    )
    (net (code "102") (name "PB5{slash}PWM1") (class "Default")
      (node (ref "JP1") (pin "11") (pinfunction "11_11") (pintype "passive"))
      (node (ref "U$1") (pin "44") (pinfunction "PB5/PWM1_44") (pintype "bidirectional"))
    )
    (net (code "103") (name "SDC0{slash}CLK") (class "Default")
      (node (ref "J1") (pin "5") (pinfunction "CLK(SCLK)_5") (pintype "bidirectional"))
      (node (ref "RN2") (pin "5") (pinfunction "2_5") (pintype "passive"))
      (node (ref "U$1") (pin "105") (pinfunction "PF2/SDC0/CLK_105") (pintype "bidirectional"))
    )
    (net (code "104") (name "SDC0{slash}CMD") (class "Default")
      (node (ref "J1") (pin "3") (pinfunction "CMD(DI)_3") (pintype "bidirectional"))
      (node (ref "RN2") (pin "6") (pinfunction "2_6") (pintype "passive"))
      (node (ref "U$1") (pin "103") (pinfunction "PF3/SDC0/CMD_103") (pintype "bidirectional"))
    )
    (net (code "105") (name "SDC0{slash}D0") (class "Default")
      (node (ref "J1") (pin "7") (pinfunction "DAT0(DO)_7") (pintype "bidirectional"))
      (node (ref "R1") (pin "1") (pinfunction "1_1") (pintype "passive"))
      (node (ref "U$1") (pin "106") (pinfunction "PF1/SDC0/D0_106") (pintype "bidirectional"))
    )
    (net (code "106") (name "SDC0{slash}D1") (class "Default")
      (node (ref "J1") (pin "8") (pinfunction "DAT1_8") (pintype "bidirectional"))
      (node (ref "R2") (pin "1") (pinfunction "1_1") (pintype "passive"))
      (node (ref "U$1") (pin "107") (pinfunction "PF0/SDC0/D1_107") (pintype "bidirectional"))
    )
    (net (code "107") (name "SDC0{slash}D2") (class "Default")
      (node (ref "J1") (pin "1") (pinfunction "DAT2_1") (pintype "bidirectional"))
      (node (ref "RN2") (pin "8") (pinfunction "2_8") (pintype "passive"))
      (node (ref "U$1") (pin "101") (pinfunction "PF5/SDC0/D2_101") (pintype "bidirectional"))
    )
    (net (code "108") (name "SDC0{slash}D3") (class "Default")
      (node (ref "J1") (pin "2") (pinfunction "CD/DAT3(~{CS})_2") (pintype "bidirectional"))
      (node (ref "RN2") (pin "7") (pinfunction "2_7") (pintype "passive"))
      (node (ref "U$1") (pin "102") (pinfunction "PF4/SDC0/D3_102") (pintype "bidirectional"))
    )
    (net (code "109") (name "SDC1{slash}CLK") (class "Default")
      (node (ref "JP2") (pin "3") (pinfunction "3_3") (pintype "passive"))
      (node (ref "U$1") (pin "5") (pinfunction "PG0/SDC1/CLK_5") (pintype "bidirectional"))
      (node (ref "U$2") (pin "P$17") (pinfunction "SDIO_CLK_P$17") (pintype "bidirectional"))
    )
    (net (code "110") (name "SDC1{slash}CMD") (class "Default")
      (node (ref "JP2") (pin "4") (pinfunction "4_4") (pintype "passive"))
      (node (ref "R36") (pin "2") (pinfunction "2_2") (pintype "passive"))
      (node (ref "U$1") (pin "4") (pinfunction "PG1/SDC1/CMD_4") (pintype "bidirectional"))
      (node (ref "U$2") (pin "P$16") (pinfunction "SDIO_CMD_P$16") (pintype "bidirectional"))
    )
    (net (code "111") (name "SDC1{slash}D0") (class "Default")
      (node (ref "JP2") (pin "2") (pinfunction "2_2") (pintype "passive"))
      (node (ref "RN1") (pin "5") (pinfunction "2_5") (pintype "passive"))
      (node (ref "U$1") (pin "3") (pinfunction "PG2/SDC1/D0_3") (pintype "bidirectional"))
      (node (ref "U$2") (pin "P$18") (pinfunction "SDIO_D0_P$18") (pintype "bidirectional"))
    )
    (net (code "112") (name "SDC1{slash}D1") (class "Default")
      (node (ref "JP2") (pin "1") (pinfunction "1_1") (pintype "passive"))
      (node (ref "RN1") (pin "6") (pinfunction "2_6") (pintype "passive"))
      (node (ref "U$1") (pin "2") (pinfunction "PG3/SDC1/D1_2") (pintype "bidirectional"))
      (node (ref "U$2") (pin "P$19") (pinfunction "SDIO_D1_P$19") (pintype "bidirectional"))
    )
    (net (code "113") (name "SDC1{slash}D2") (class "Default")
      (node (ref "JP2") (pin "6") (pinfunction "6_6") (pintype "passive"))
      (node (ref "RN1") (pin "7") (pinfunction "2_7") (pintype "passive"))
      (node (ref "U$1") (pin "1") (pinfunction "PG4/SDC1/D2_1") (pintype "bidirectional"))
      (node (ref "U$2") (pin "P$14") (pinfunction "SDIO_D2_P$14") (pintype "bidirectional"))
    )
    (net (code "114") (name "SDC1{slash}D3") (class "Default")
      (node (ref "JP2") (pin "5") (pinfunction "5_5") (pintype "passive"))
      (node (ref "RN1") (pin "8") (pinfunction "2_8") (pintype "passive"))
      (node (ref "U$1") (pin "128") (pinfunction "PG5/SDC1/D3_128") (pintype "bidirectional"))
      (node (ref "U$2") (pin "P$15") (pinfunction "SDIO_D3_P$15") (pintype "bidirectional"))
    )
    (net (code "115") (name "SPD_LED") (class "Default")
      (node (ref "R52") (pin "1") (pinfunction "1_1") (pintype "passive"))
      (node (ref "U$1") (pin "78") (pinfunction "EPHY_SPD_LED_78") (pintype "bidirectional"))
    )
    (net (code "116") (name "SPI1{slash}CS") (class "Default")
      (node (ref "JP1") (pin "24") (pinfunction "24_24") (pintype "passive"))
      (node (ref "R8") (pin "1") (pinfunction "1_1") (pintype "passive"))
      (node (ref "U$1") (pin "54") (pinfunction "PC2/SPI1/CS_54") (pintype "bidirectional"))
      (node (ref "U1") (pin "1") (pinfunction "CS_1") (pintype "bidirectional"))
    )
    (net (code "117") (name "SPI1{slash}MISO") (class "Default")
      (node (ref "JP1") (pin "21") (pinfunction "21_21") (pintype "passive"))
      (node (ref "U$1") (pin "52") (pinfunction "PC0/SPI1/MISO_52") (pintype "bidirectional"))
      (node (ref "U1") (pin "2") (pinfunction "MISO_2") (pintype "bidirectional"))
    )
    (net (code "118") (name "SPI1{slash}MOSI") (class "Default")
      (node (ref "JP1") (pin "19") (pinfunction "19_19") (pintype "passive"))
      (node (ref "U$1") (pin "55") (pinfunction "PC3/SPI1/MOSI_55") (pintype "bidirectional"))
      (node (ref "U1") (pin "5") (pinfunction "MOSI_5") (pintype "bidirectional"))
    )
    (net (code "119") (name "SPI1{slash}SCK") (class "Default")
      (node (ref "JP1") (pin "23") (pinfunction "23_23") (pintype "passive"))
      (node (ref "U$1") (pin "53") (pinfunction "PC1/SPI1/SCK_53") (pintype "bidirectional"))
      (node (ref "U1") (pin "6") (pinfunction "SCK_6") (pintype "bidirectional"))
    )
    (net (code "120") (name "SVREF") (class "Default")
      (node (ref "C14") (pin "1") (pinfunction "1_1") (pintype "passive"))
      (node (ref "C15") (pin "2") (pinfunction "2_2") (pintype "passive"))
      (node (ref "R13") (pin "1") (pinfunction "1_1") (pintype "passive"))
      (node (ref "R14") (pin "2") (pinfunction "2_2") (pintype "passive"))
      (node (ref "U$1") (pin "63") (pinfunction "SVREF1_63") (pintype "bidirectional"))
      (node (ref "U$1") (pin "71") (pinfunction "SVREF0_71") (pintype "bidirectional"))
    )
    (net (code "121") (name "TPX1") (class "Default")
      (node (ref "J3") (pin "37") (pinfunction "MS_37") (pintype "passive"))
      (node (ref "U$8") (pin "2") (pinfunction "XP_2") (pintype "bidirectional"))
    )
    (net (code "122") (name "TPX2") (class "Default")
      (node (ref "J3") (pin "39") (pinfunction "MS_39") (pintype "passive"))
      (node (ref "U$8") (pin "4") (pinfunction "XN_4") (pintype "bidirectional"))
    )
    (net (code "123") (name "TPY1") (class "Default")
      (node (ref "J3") (pin "38") (pinfunction "MS_38") (pintype "passive"))
      (node (ref "U$8") (pin "3") (pinfunction "YP_3") (pintype "bidirectional"))
    )
    (net (code "124") (name "TPY2") (class "Default")
      (node (ref "J3") (pin "40") (pinfunction "MS_40") (pintype "passive"))
      (node (ref "U$8") (pin "5") (pinfunction "YN_5") (pintype "bidirectional"))
    )
    (net (code "125") (name "UART0{slash}RX") (class "Default")
      (node (ref "JP1") (pin "10") (pinfunction "10_10") (pintype "passive"))
      (node (ref "U$1") (pin "49") (pinfunction "PB9/I2C1/SDA_49") (pintype "bidirectional"))
    )
    (net (code "126") (name "UART0{slash}TX") (class "Default")
      (node (ref "JP1") (pin "8") (pinfunction "8_8") (pintype "passive"))
      (node (ref "U$1") (pin "48") (pinfunction "PB8/I2C1/SCL_48") (pintype "bidirectional"))
    )
    (net (code "127") (name "UART2{slash}RX{slash}PB1") (class "Default")
      (node (ref "JP1") (pin "16") (pinfunction "16_16") (pintype "passive"))
      (node (ref "U$1") (pin "40") (pinfunction "PB1/UART2/RX_40") (pintype "bidirectional"))
    )
    (net (code "128") (name "UART2{slash}TX{slash}PB0") (class "Default")
      (node (ref "JP1") (pin "18") (pinfunction "18_18") (pintype "passive"))
      (node (ref "U$1") (pin "39") (pinfunction "PB0/UART2/TX_39") (pintype "bidirectional"))
    )
    (net (code "129") (name "USB_DM") (class "Default")
      (node (ref "U$1") (pin "110") (pinfunction "USB-DM_110") (pintype "bidirectional"))
      (node (ref "U$5") (pin "2") (pinfunction "2_2") (pintype "input"))
      (node (ref "X1") (pin "D-") (pinfunction "D-_D-") (pintype "bidirectional"))
    )
    (net (code "130") (name "USB_DP") (class "Default")
      (node (ref "U$1") (pin "111") (pinfunction "USB-DP_111") (pintype "bidirectional"))
      (node (ref "U$5") (pin "3") (pinfunction "3_3") (pintype "input"))
      (node (ref "X1") (pin "D+") (pinfunction "D+_D+") (pintype "bidirectional"))
    )
    (net (code "131") (name "USB{slash}ID") (class "Default")
      (node (ref "R32") (pin "2") (pinfunction "2_2") (pintype "passive"))
      (node (ref "U$1") (pin "100") (pinfunction "PF6_100") (pintype "bidirectional"))
      (node (ref "U$5") (pin "4") (pinfunction "4_4") (pintype "input"))
    )
    (net (code "132") (name "VCC-PE") (class "Default")
      (node (ref "JP3") (pin "2") (pinfunction "2_2") (pintype "passive"))
      (node (ref "R44") (pin "1") (pinfunction "1_1") (pintype "passive"))
      (node (ref "R45") (pin "1") (pinfunction "1_1") (pintype "passive"))
      (node (ref "U$1") (pin "12") (pinfunction "VCC-PE0_12") (pintype "bidirectional"))
      (node (ref "U$1") (pin "29") (pinfunction "VCC-PE1_29") (pintype "bidirectional"))
    )
    (net (code "133") (name "VLED+") (class "Default")
      (node (ref "C74") (pin "1") (pinfunction "1_1") (pintype "passive"))
      (node (ref "C75") (pin "1") (pinfunction "1_1") (pintype "passive"))
      (node (ref "D1") (pin "C") (pinfunction "C_C") (pintype "passive"))
      (node (ref "J3") (pin "2") (pinfunction "MS_2") (pintype "passive"))
      (node (ref "U$9") (pin "5") (pinfunction "OV_5") (pintype "bidirectional"))
    )
    (net (code "134") (name "VLED-") (class "Default")
      (node (ref "J3") (pin "1") (pinfunction "MSV_1") (pintype "passive"))
      (node (ref "R47") (pin "1") (pinfunction "1_1") (pintype "passive"))
      (node (ref "U$9") (pin "3") (pinfunction "FB_3") (pintype "bidirectional"))
    )
    (net (code "135") (name "VRA1") (class "Default")
      (node (ref "C21") (pin "2") (pinfunction "2_2") (pintype "passive"))
      (node (ref "U$1") (pin "117") (pinfunction "VRA1_117") (pintype "bidirectional"))
    )
    (net (code "136") (name "VRA2") (class "Default")
      (node (ref "C20") (pin "2") (pinfunction "2_2") (pintype "passive"))
      (node (ref "R27") (pin "2") (pinfunction "2_2") (pintype "passive"))
      (node (ref "U$1") (pin "118") (pinfunction "VRA2_118") (pintype "bidirectional"))
    )
    (net (code "137") (name "WL_H_WK") (class "Default")
      (node (ref "U$2") (pin "P$13") (pinfunction "WL_H_WK_P$13") (pintype "bidirectional"))
    )
    (net (code "138") (name "unconnected-(U$2-BTXTALOUT-PadP$38)") (class "Default")
      (node (ref "U$2") (pin "P$38") (pinfunction "BTXTALOUT_P$38") (pintype "bidirectional"))
    )
    (net (code "139") (name "unconnected-(U$2-BT_XTAL_IN-PadP$37)") (class "Default")
      (node (ref "U$2") (pin "P$37") (pinfunction "BT_XTAL_IN_P$37") (pintype "bidirectional"))
    )
    (net (code "140") (name "unconnected-(U$2-LPO-PadP$24)") (class "Default")
      (node (ref "U$2") (pin "P$24") (pinfunction "LPO_P$24") (pintype "bidirectional"))
    )
    (net (code "141") (name "unconnected-(U$2-NC4-PadP$4)") (class "Default")
      (node (ref "U$2") (pin "P$4") (pinfunction "NC4_P$4") (pintype "bidirectional"))
    )
    (net (code "142") (name "unconnected-(U$2-NC5-PadP$5)") (class "Default")
      (node (ref "U$2") (pin "P$5") (pinfunction "NC5_P$5") (pintype "bidirectional"))
    )
    (net (code "143") (name "unconnected-(U$2-NC8-PadP$8)") (class "Default")
      (node (ref "U$2") (pin "P$8") (pinfunction "NC8_P$8") (pintype "bidirectional"))
    )
    (net (code "144") (name "unconnected-(U$2-NC32-PadP$32)") (class "Default")
      (node (ref "U$2") (pin "P$32") (pinfunction "NC32_P$32") (pintype "bidirectional"))
    )
    (net (code "145") (name "unconnected-(U$2-NC35-PadP$35)") (class "Default")
      (node (ref "U$2") (pin "P$35") (pinfunction "NC35_P$35") (pintype "bidirectional"))
    )
    (net (code "146") (name "unconnected-(U$2-NC39-PadP$39)") (class "Default")
      (node (ref "U$2") (pin "P$39") (pinfunction "NC39_P$39") (pintype "bidirectional"))
    )
    (net (code "147") (name "unconnected-(U$2-NC40-PadP$40)") (class "Default")
      (node (ref "U$2") (pin "P$40") (pinfunction "NC40_P$40") (pintype "bidirectional"))
    )
    (net (code "148") (name "unconnected-(U$2-PCM_CLK-PadP$26)") (class "Default")
      (node (ref "U$2") (pin "P$26") (pinfunction "PCM_CLK_P$26") (pintype "bidirectional"))
    )
    (net (code "149") (name "unconnected-(U$2-PCM_IN-PadP$27)") (class "Default")
      (node (ref "U$2") (pin "P$27") (pinfunction "PCM_IN_P$27") (pintype "bidirectional"))
    )
    (net (code "150") (name "unconnected-(U$2-PCM_OUT-PadP$25)") (class "Default")
      (node (ref "U$2") (pin "P$25") (pinfunction "PCM_OUT_P$25") (pintype "bidirectional"))
    )
    (net (code "151") (name "unconnected-(U$2-PCM_SYNC-PadP$28)") (class "Default")
      (node (ref "U$2") (pin "P$28") (pinfunction "PCM_SYNC_P$28") (pintype "bidirectional"))
    )
    (net (code "152") (name "unconnected-(U$2-TCXO_IN-PadP$30)") (class "Default")
      (node (ref "U$2") (pin "P$30") (pinfunction "TCXO_IN_P$30") (pintype "bidirectional"))
    )
    (net (code "153") (name "unconnected-(U$2-VDD_TXCO-PadP$29)") (class "Default")
      (node (ref "U$2") (pin "P$29") (pinfunction "VDD_TXCO_P$29") (pintype "bidirectional"))
    )
    (net (code "154") (name "unconnected-(U$2-VIN_LDO_OUT-PadP$21)") (class "Default")
      (node (ref "U$2") (pin "P$21") (pinfunction "VIN_LDO_OUT_P$21") (pintype "bidirectional"))
    )
    (net (code "155") (name "unconnected-(U$2-XTAL_WL_IN-PadP$10)") (class "Default")
      (node (ref "U$2") (pin "P$10") (pinfunction "XTAL_WL_IN_P$10") (pintype "bidirectional"))
    )
    (net (code "156") (name "unconnected-(U$2-XTAL_WL_OUT-PadP$11)") (class "Default")
      (node (ref "U$2") (pin "P$11") (pinfunction "XTAL_WL_OUT_P$11") (pintype "bidirectional"))
    )
    (net (code "157") (name "unconnected-(U$3-NC-Pad7)") (class "Default")
      (node (ref "U$3") (pin "7") (pinfunction "NC_7") (pintype "bidirectional"))
    )
    (net (code "158") (name "unconnected-(U$8-PENIRQ-Pad7)") (class "Default")
      (node (ref "U$8") (pin "7") (pinfunction "PENIRQ_7") (pintype "bidirectional"))
    )
  )
)
